# motor_board.net
KiCad netlist of a schematic drawn in EAGLE
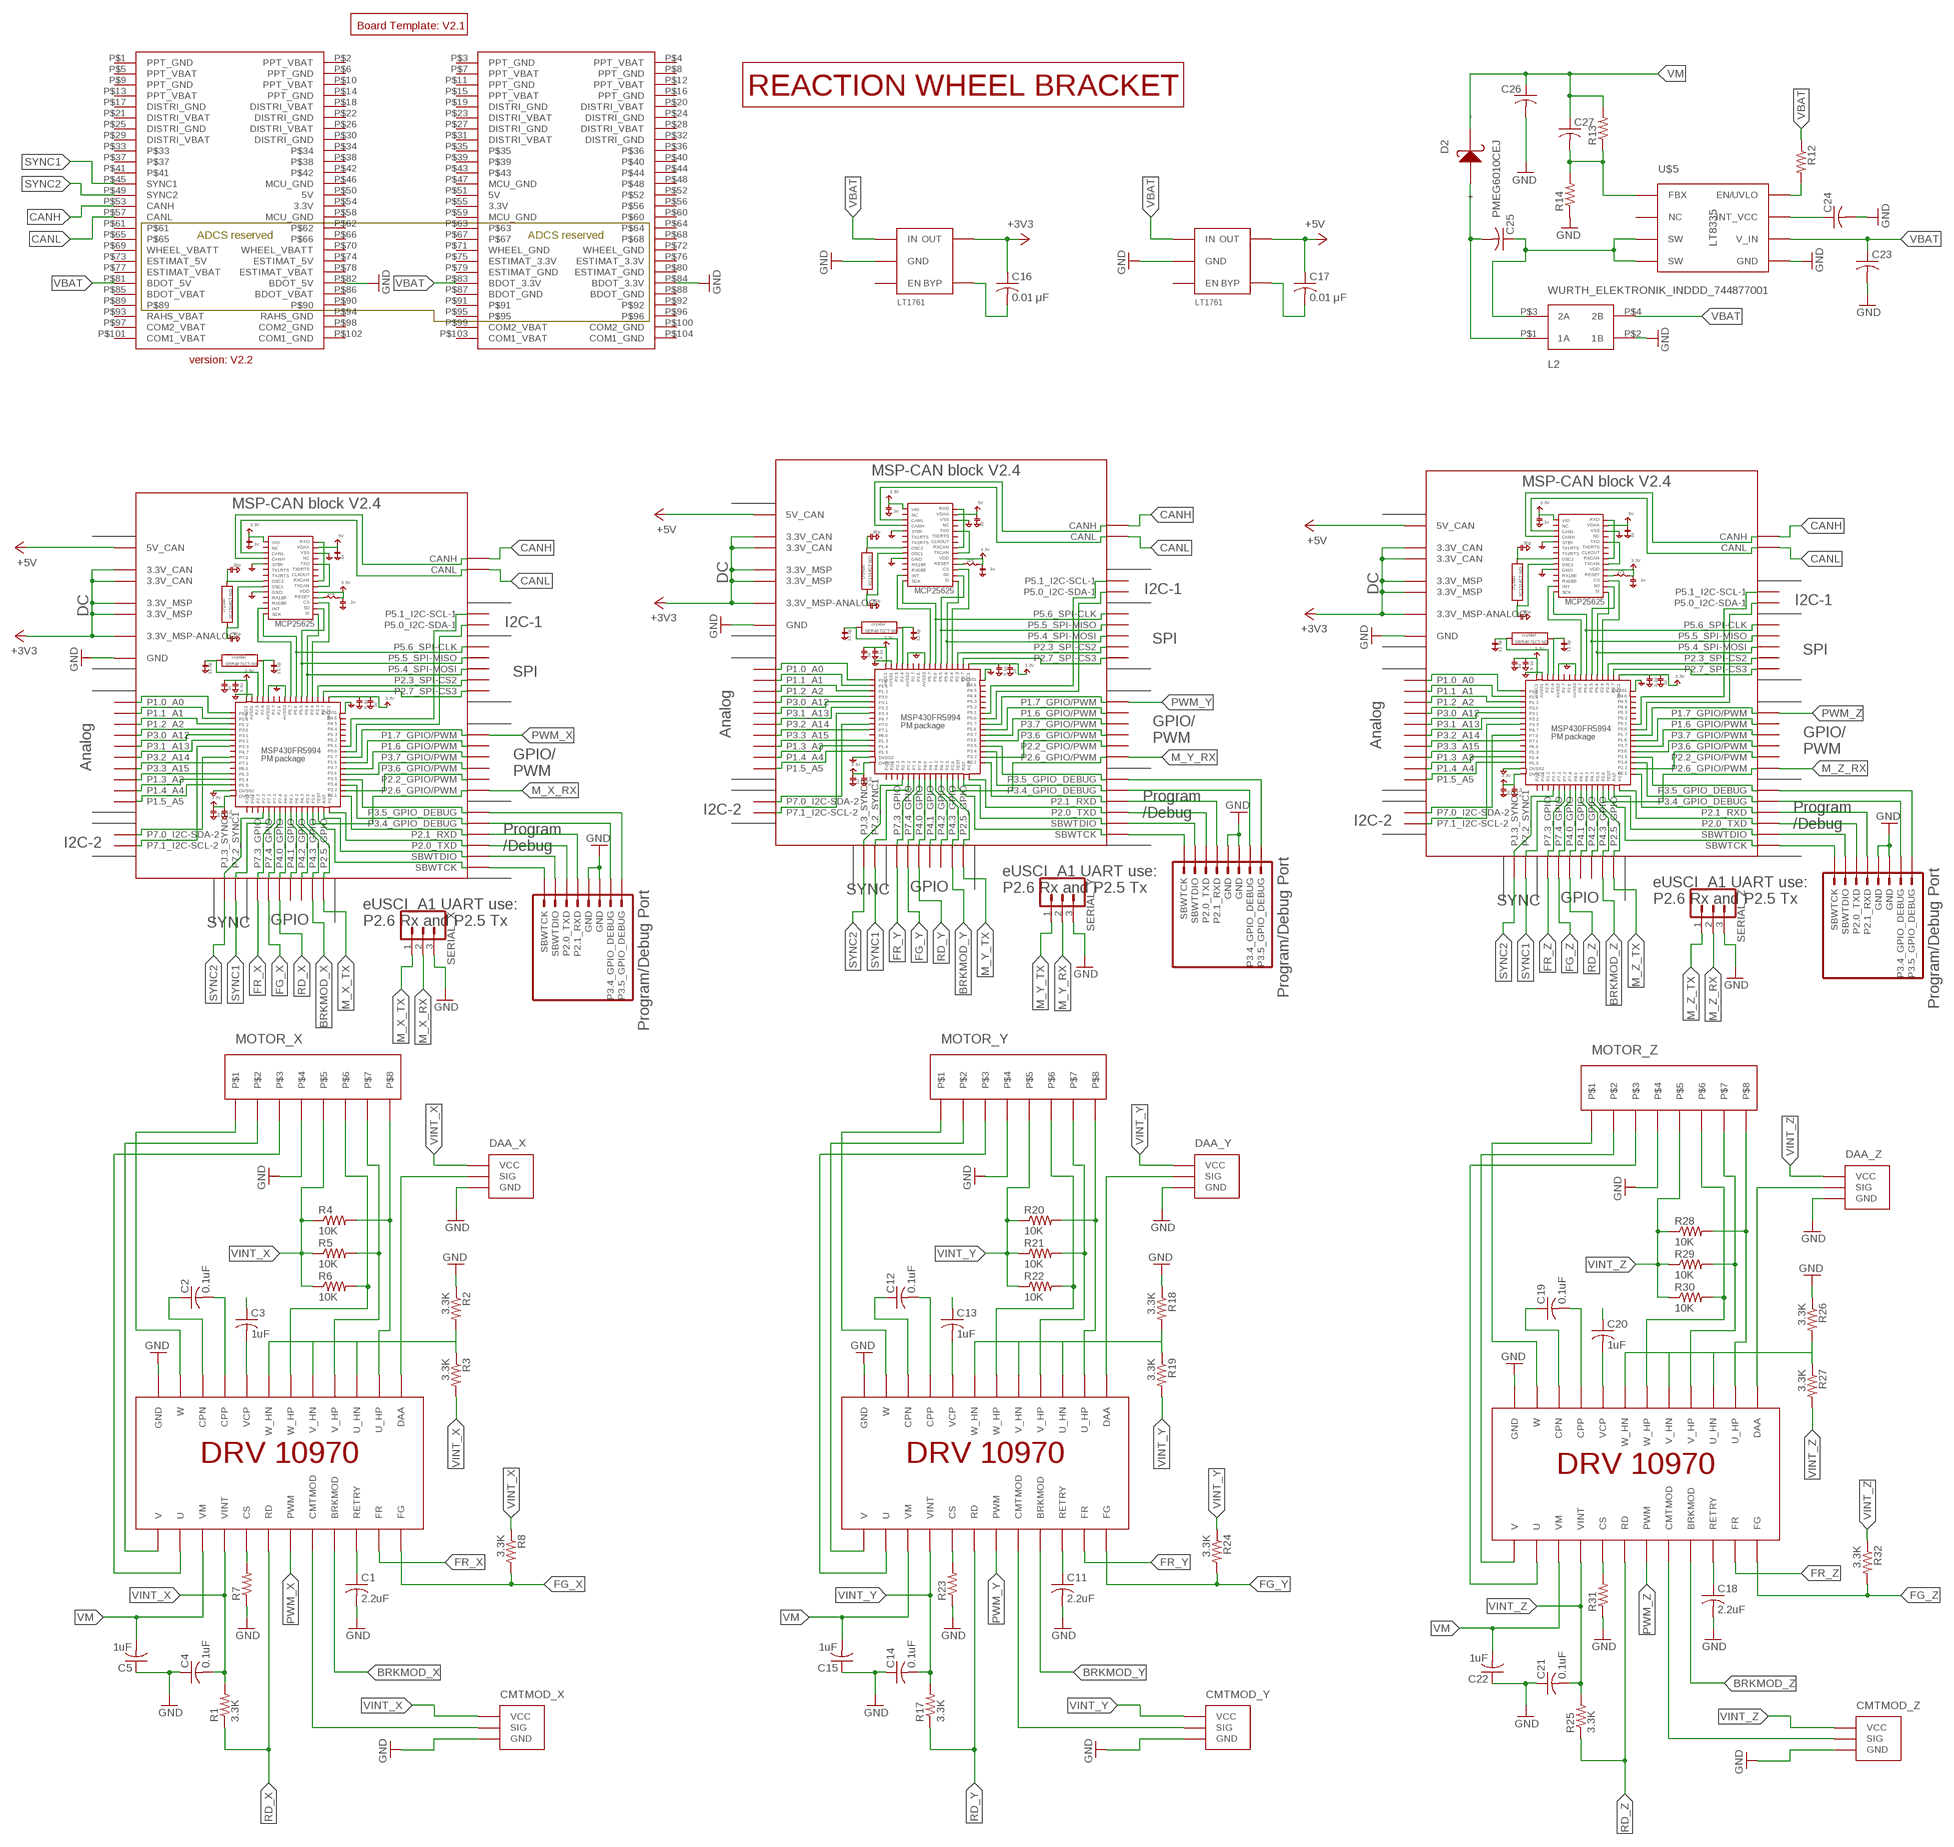
[diagram p0: schematic, sheet 1]

(export (version "E")
  (design (tool "Eeschema 10.0.6"))
  (components
    (comp (ref "C1")
      (value "2.2uF")
      (footprint "eagle-import:C1206")
      (libsource (lib "eagle-import") (part "C-USC1206"))
    )
    (comp (ref "C2")
      (value "0.1uF")
      (footprint "eagle-import:C0805")
      (libsource (lib "eagle-import") (part "C-USC0805"))
    )
    (comp (ref "C3")
      (value "1uF")
      (footprint "eagle-import:C1206")
      (libsource (lib "eagle-import") (part "C-USC1206"))
    )
    (comp (ref "C4")
      (value "0.1uF")
      (footprint "eagle-import:C0805")
      (libsource (lib "eagle-import") (part "C-USC0805"))
    )
    (comp (ref "C5")
      (value "1uF")
      (footprint "eagle-import:C1206")
      (libsource (lib "eagle-import") (part "C-USC1206"))
    )
    (comp (ref "C11")
      (value "2.2uF")
      (footprint "eagle-import:C1206")
      (libsource (lib "eagle-import") (part "C-USC1206"))
    )
    (comp (ref "C12")
      (value "0.1uF")
      (footprint "eagle-import:C0805")
      (libsource (lib "eagle-import") (part "C-USC0805"))
    )
    (comp (ref "C13")
      (value "1uF")
      (footprint "eagle-import:C1206")
      (libsource (lib "eagle-import") (part "C-USC1206"))
    )
    (comp (ref "C14")
      (value "0.1uF")
      (footprint "eagle-import:C0805")
      (libsource (lib "eagle-import") (part "C-USC0805"))
    )
    (comp (ref "C15")
      (value "1uF")
      (footprint "eagle-import:C1206")
      (libsource (lib "eagle-import") (part "C-USC1206"))
    )
    (comp (ref "C16")
      (value "0.01 μF")
      (footprint "eagle-import:C0805")
      (libsource (lib "eagle-import") (part "C-USC0805"))
    )
    (comp (ref "C17")
      (value "0.01 μF")
      (footprint "eagle-import:C0805")
      (libsource (lib "eagle-import") (part "C-USC0805"))
    )
    (comp (ref "C18")
      (value "2.2uF")
      (footprint "eagle-import:C1206")
      (libsource (lib "eagle-import") (part "C-USC1206"))
    )
    (comp (ref "C19")
      (value "0.1uF")
      (footprint "eagle-import:C0805")
      (libsource (lib "eagle-import") (part "C-USC0805"))
    )
    (comp (ref "C20")
      (value "1uF")
      (footprint "eagle-import:C1206")
      (libsource (lib "eagle-import") (part "C-USC1206"))
    )
    (comp (ref "C21")
      (value "0.1uF")
      (footprint "eagle-import:C0805")
      (libsource (lib "eagle-import") (part "C-USC0805"))
    )
    (comp (ref "C22")
      (value "1uF")
      (footprint "eagle-import:C1206")
      (libsource (lib "eagle-import") (part "C-USC1206"))
    )
    (comp (ref "C23")
      (value "C-USC0805")
      (footprint "eagle-import:C0805")
      (libsource (lib "eagle-import") (part "C-USC0805"))
    )
    (comp (ref "C24")
      (value "C-USC0805")
      (footprint "eagle-import:C0805")
      (libsource (lib "eagle-import") (part "C-USC0805"))
    )
    (comp (ref "C25")
      (value "C-USC0805")
      (footprint "eagle-import:C0805")
      (libsource (lib "eagle-import") (part "C-USC0805"))
    )
    (comp (ref "C26")
      (value "C-USC0805")
      (footprint "eagle-import:C0805")
      (libsource (lib "eagle-import") (part "C-USC0805"))
    )
    (comp (ref "C27")
      (value "C-USC0805")
      (footprint "eagle-import:C0805")
      (libsource (lib "eagle-import") (part "C-USC0805"))
    )
    (comp (ref "CMTMOD_X")
      (value "0_OHM_JUMPER")
      (footprint "eagle-import:0_OHM_JUMPER")
      (libsource (lib "eagle-import") (part "0_OHM_JUMPER"))
    )
    (comp (ref "CMTMOD_Y")
      (value "0_OHM_JUMPER")
      (footprint "eagle-import:0_OHM_JUMPER")
      (libsource (lib "eagle-import") (part "0_OHM_JUMPER"))
    )
    (comp (ref "CMTMOD_Z")
      (value "0_OHM_JUMPER")
      (footprint "eagle-import:0_OHM_JUMPER")
      (libsource (lib "eagle-import") (part "0_OHM_JUMPER"))
    )
    (comp (ref "D2")
      (value "PMEG6010CEJ")
      (footprint "eagle-import:SC-90")
      (libsource (lib "eagle-import") (part "PMEG6010CEJ"))
    )
    (comp (ref "DAA_X")
      (value "0_OHM_JUMPER")
      (footprint "eagle-import:0_OHM_JUMPER")
      (libsource (lib "eagle-import") (part "0_OHM_JUMPER"))
    )
    (comp (ref "DAA_Y")
      (value "0_OHM_JUMPER")
      (footprint "eagle-import:0_OHM_JUMPER")
      (libsource (lib "eagle-import") (part "0_OHM_JUMPER"))
    )
    (comp (ref "DAA_Z")
      (value "0_OHM_JUMPER")
      (footprint "eagle-import:0_OHM_JUMPER")
      (libsource (lib "eagle-import") (part "0_OHM_JUMPER"))
    )
    (comp (ref "L2")
      (value "WURTH_ELEKTRONIK_INDDD_744877001")
      (footprint "eagle-import:WURTH_ELEKTRONIK_INDDD_744877001")
      (libsource (lib "eagle-import") (part "WURTH_ELEKTRONIK_INDDD_744877001"))
    )
    (comp (ref "LDO_3V3")
      (value "LINEAR_LDO_LT1761-X")
      (footprint "eagle-import:SOT-23-5")
      (libsource (lib "eagle-import") (part "LINEAR_LDO_LT1761-X"))
    )
    (comp (ref "LDO_5V")
      (value "LINEAR_LDO_LT1761-X")
      (footprint "eagle-import:SOT-23-5")
      (libsource (lib "eagle-import") (part "LINEAR_LDO_LT1761-X"))
    )
    (comp (ref "MOTOR_X")
      (value "PICOLOCK_8")
      (footprint "eagle-import:PICOLOCK_8")
      (libsource (lib "eagle-import") (part "PICOLOCK_8"))
    )
    (comp (ref "MOTOR_Y")
      (value "PICOLOCK_8")
      (footprint "eagle-import:PICOLOCK_8")
      (libsource (lib "eagle-import") (part "PICOLOCK_8"))
    )
    (comp (ref "MOTOR_Z")
      (value "PICOLOCK_8")
      (footprint "eagle-import:PICOLOCK_8")
      (libsource (lib "eagle-import") (part "PICOLOCK_8"))
    )
    (comp (ref "R1")
      (value "3.3K")
      (footprint "eagle-import:R0805")
      (libsource (lib "eagle-import") (part "R-US_R0805"))
    )
    (comp (ref "R2")
      (value "3.3K")
      (footprint "eagle-import:R0805")
      (libsource (lib "eagle-import") (part "R-US_R0805"))
    )
    (comp (ref "R3")
      (value "3.3K")
      (footprint "eagle-import:R0805")
      (libsource (lib "eagle-import") (part "R-US_R0805"))
    )
    (comp (ref "R4")
      (value "10K")
      (footprint "eagle-import:R0805")
      (libsource (lib "eagle-import") (part "R-US_R0805"))
    )
    (comp (ref "R5")
      (value "10K")
      (footprint "eagle-import:R0805")
      (libsource (lib "eagle-import") (part "R-US_R0805"))
    )
    (comp (ref "R6")
      (value "10K")
      (footprint "eagle-import:R0805")
      (libsource (lib "eagle-import") (part "R-US_R0805"))
    )
    (comp (ref "R7")
      (value "R-US_R0805")
      (footprint "eagle-import:R0805")
      (libsource (lib "eagle-import") (part "R-US_R0805"))
    )
    (comp (ref "R8")
      (value "3.3K")
      (footprint "eagle-import:R0805")
      (libsource (lib "eagle-import") (part "R-US_R0805"))
    )
    (comp (ref "R12")
      (value "R-US_R0805")
      (footprint "eagle-import:R0805")
      (libsource (lib "eagle-import") (part "R-US_R0805"))
    )
    (comp (ref "R13")
      (value "R-US_R0805")
      (footprint "eagle-import:R0805")
      (libsource (lib "eagle-import") (part "R-US_R0805"))
    )
    (comp (ref "R14")
      (value "R-US_R0805")
      (footprint "eagle-import:R0805")
      (libsource (lib "eagle-import") (part "R-US_R0805"))
    )
    (comp (ref "R17")
      (value "3.3K")
      (footprint "eagle-import:R0805")
      (libsource (lib "eagle-import") (part "R-US_R0805"))
    )
    (comp (ref "R18")
      (value "3.3K")
      (footprint "eagle-import:R0805")
      (libsource (lib "eagle-import") (part "R-US_R0805"))
    )
    (comp (ref "R19")
      (value "3.3K")
      (footprint "eagle-import:R0805")
      (libsource (lib "eagle-import") (part "R-US_R0805"))
    )
    (comp (ref "R20")
      (value "10K")
      (footprint "eagle-import:R0805")
      (libsource (lib "eagle-import") (part "R-US_R0805"))
    )
    (comp (ref "R21")
      (value "10K")
      (footprint "eagle-import:R0805")
      (libsource (lib "eagle-import") (part "R-US_R0805"))
    )
    (comp (ref "R22")
      (value "10K")
      (footprint "eagle-import:R0805")
      (libsource (lib "eagle-import") (part "R-US_R0805"))
    )
    (comp (ref "R23")
      (value "R-US_R0805")
      (footprint "eagle-import:R0805")
      (libsource (lib "eagle-import") (part "R-US_R0805"))
    )
    (comp (ref "R24")
      (value "3.3K")
      (footprint "eagle-import:R0805")
      (libsource (lib "eagle-import") (part "R-US_R0805"))
    )
    (comp (ref "R25")
      (value "3.3K")
      (footprint "eagle-import:R0805")
      (libsource (lib "eagle-import") (part "R-US_R0805"))
    )
    (comp (ref "R26")
      (value "3.3K")
      (footprint "eagle-import:R0805")
      (libsource (lib "eagle-import") (part "R-US_R0805"))
    )
    (comp (ref "R27")
      (value "3.3K")
      (footprint "eagle-import:R0805")
      (libsource (lib "eagle-import") (part "R-US_R0805"))
    )
    (comp (ref "R28")
      (value "10K")
      (footprint "eagle-import:R0805")
      (libsource (lib "eagle-import") (part "R-US_R0805"))
    )
    (comp (ref "R29")
      (value "10K")
      (footprint "eagle-import:R0805")
      (libsource (lib "eagle-import") (part "R-US_R0805"))
    )
    (comp (ref "R30")
      (value "10K")
      (footprint "eagle-import:R0805")
      (libsource (lib "eagle-import") (part "R-US_R0805"))
    )
    (comp (ref "R31")
      (value "R-US_R0805")
      (footprint "eagle-import:R0805")
      (libsource (lib "eagle-import") (part "R-US_R0805"))
    )
    (comp (ref "R32")
      (value "3.3K")
      (footprint "eagle-import:R0805")
      (libsource (lib "eagle-import") (part "R-US_R0805"))
    )
    (comp (ref "SERIAL_X")
      (value "CONN_03LOCK")
      (footprint "eagle-import:1X03_LOCK")
      (libsource (lib "eagle-import") (part "CONN_03LOCK"))
    )
    (comp (ref "SERIAL_Y")
      (value "CONN_03LOCK")
      (footprint "eagle-import:1X03_LOCK")
      (libsource (lib "eagle-import") (part "CONN_03LOCK"))
    )
    (comp (ref "SERIAL_Z")
      (value "CONN_03LOCK")
      (footprint "eagle-import:1X03_LOCK")
      (libsource (lib "eagle-import") (part "CONN_03LOCK"))
    )
    (comp (ref "U$1")
      (value "BOARD_TEMPLATE")
      (footprint "eagle-import:BOARD_TEMPLATE")
      (libsource (lib "eagle-import") (part "BOARD_TEMPLATE"))
    )
    (comp (ref "U$2")
      (value "PC104_CONNECTOR")
      (footprint "eagle-import:PC104_CONNECTOR")
      (libsource (lib "eagle-import") (part "PC104_CONNECTOR"))
    )
    (comp (ref "U$3")
      (value "MSP-CAN_BLOCK")
      (footprint "eagle-import:MSP-CAN_BLOCK")
      (libsource (lib "eagle-import") (part "MSP-CAN_BLOCK"))
    )
    (comp (ref "U$4")
      (value "PROGRAM/DEBUG_PORT")
      (footprint "eagle-import:1X08_CONNECTOR")
      (libsource (lib "eagle-import") (part "PROGRAM/DEBUG_PORT"))
    )
    (comp (ref "U$5")
      (value "LT8335")
      (footprint "eagle-import:DDB")
      (libsource (lib "eagle-import") (part "LT8335"))
    )
    (comp (ref "U$7")
      (value "DRV10970")
      (footprint "eagle-import:DRV10970")
      (libsource (lib "eagle-import") (part "DRV10970"))
    )
    (comp (ref "U$9")
      (value "REACTION_WHEEL_BRACKET")
      (footprint "eagle-import:REACTION_WHEEL_BRACKET")
      (libsource (lib "eagle-import") (part "REACTION_WHEEL_BRACKET"))
    )
    (comp (ref "U$10")
      (value "MSP-CAN_BLOCK")
      (footprint "eagle-import:MSP-CAN_BLOCK")
      (libsource (lib "eagle-import") (part "MSP-CAN_BLOCK"))
    )
    (comp (ref "U$11")
      (value "PROGRAM/DEBUG_PORT")
      (footprint "eagle-import:1X08_CONNECTOR")
      (libsource (lib "eagle-import") (part "PROGRAM/DEBUG_PORT"))
    )
    (comp (ref "U$12")
      (value "DRV10970")
      (footprint "eagle-import:DRV10970")
      (libsource (lib "eagle-import") (part "DRV10970"))
    )
    (comp (ref "U$13")
      (value "MSP-CAN_BLOCK")
      (footprint "eagle-import:MSP-CAN_BLOCK")
      (libsource (lib "eagle-import") (part "MSP-CAN_BLOCK"))
    )
    (comp (ref "U$14")
      (value "PROGRAM/DEBUG_PORT")
      (footprint "eagle-import:1X08_CONNECTOR")
      (libsource (lib "eagle-import") (part "PROGRAM/DEBUG_PORT"))
    )
    (comp (ref "U$15")
      (value "DRV10970")
      (footprint "eagle-import:DRV10970")
      (libsource (lib "eagle-import") (part "DRV10970"))
    )
  )
  (nets
    (net (code "1") (name "+3V3") (class "Default")
      (node (ref "C16") (pin "1") (pinfunction "1_1") (pintype "passive"))
      (node (ref "LDO_3V3") (pin "P$5") (pinfunction "OUT_P$5") (pintype "bidirectional"))
      (node (ref "U$10") (pin "3.3V@CAN1") (pinfunction "3.3V_CAN_3.3V@CAN1") (pintype "bidirectional"))
      (node (ref "U$10") (pin "3.3V@CAN2") (pinfunction "3.3V_CAN_3.3V@CAN2") (pintype "bidirectional"))
      (node (ref "U$10") (pin "3.3V@MSP1") (pinfunction "3.3V_MSP_3.3V@MSP1") (pintype "bidirectional"))
      (node (ref "U$10") (pin "3.3V@MSP2") (pinfunction "3.3V_MSP_3.3V@MSP2") (pintype "bidirectional"))
      (node (ref "U$10") (pin "3.3V_ANALOG@MSP2") (pinfunction "3.3V_MSP-ANALOG_3.3V_ANALOG@MSP2") (pintype "bidirectional"))
      (node (ref "U$13") (pin "3.3V@CAN1") (pinfunction "3.3V_CAN_3.3V@CAN1") (pintype "bidirectional"))
      (node (ref "U$13") (pin "3.3V@CAN2") (pinfunction "3.3V_CAN_3.3V@CAN2") (pintype "bidirectional"))
      (node (ref "U$13") (pin "3.3V@MSP1") (pinfunction "3.3V_MSP_3.3V@MSP1") (pintype "bidirectional"))
      (node (ref "U$13") (pin "3.3V@MSP2") (pinfunction "3.3V_MSP_3.3V@MSP2") (pintype "bidirectional"))
      (node (ref "U$13") (pin "3.3V_ANALOG@MSP2") (pinfunction "3.3V_MSP-ANALOG_3.3V_ANALOG@MSP2") (pintype "bidirectional"))
      (node (ref "U$3") (pin "3.3V@CAN1") (pinfunction "3.3V_CAN_3.3V@CAN1") (pintype "bidirectional"))
      (node (ref "U$3") (pin "3.3V@CAN2") (pinfunction "3.3V_CAN_3.3V@CAN2") (pintype "bidirectional"))
      (node (ref "U$3") (pin "3.3V@MSP1") (pinfunction "3.3V_MSP_3.3V@MSP1") (pintype "bidirectional"))
      (node (ref "U$3") (pin "3.3V@MSP2") (pinfunction "3.3V_MSP_3.3V@MSP2") (pintype "bidirectional"))
      (node (ref "U$3") (pin "3.3V_ANALOG@MSP2") (pinfunction "3.3V_MSP-ANALOG_3.3V_ANALOG@MSP2") (pintype "bidirectional"))
    )
    (net (code "2") (name "+5V") (class "Default")
      (node (ref "C17") (pin "1") (pinfunction "1_1") (pintype "passive"))
      (node (ref "LDO_5V") (pin "P$5") (pinfunction "OUT_P$5") (pintype "bidirectional"))
      (node (ref "U$10") (pin "5V") (pinfunction "5V_CAN_5V") (pintype "bidirectional"))
      (node (ref "U$13") (pin "5V") (pinfunction "5V_CAN_5V") (pintype "bidirectional"))
      (node (ref "U$3") (pin "5V") (pinfunction "5V_CAN_5V") (pintype "bidirectional"))
    )
    (net (code "3") (name "BRKMOD_X") (class "Default")
      (node (ref "U$3") (pin "P4.3_GPIO") (pinfunction "P4.3_GPIO_P4.3_GPIO") (pintype "bidirectional"))
      (node (ref "U$7") (pin "BRKMOD") (pinfunction "BRKMOD_BRKMOD") (pintype "bidirectional"))
    )
    (net (code "4") (name "BRKMOD_Y") (class "Default")
      (node (ref "U$10") (pin "P4.3_GPIO") (pinfunction "P4.3_GPIO_P4.3_GPIO") (pintype "bidirectional"))
      (node (ref "U$12") (pin "BRKMOD") (pinfunction "BRKMOD_BRKMOD") (pintype "bidirectional"))
    )
    (net (code "5") (name "BRKMOD_Z") (class "Default")
      (node (ref "U$13") (pin "P4.3_GPIO") (pinfunction "P4.3_GPIO_P4.3_GPIO") (pintype "bidirectional"))
      (node (ref "U$15") (pin "BRKMOD") (pinfunction "BRKMOD_BRKMOD") (pintype "bidirectional"))
    )
    (net (code "6") (name "CANH") (class "Default")
      (node (ref "U$10") (pin "CANH") (pinfunction "CANH_CANH") (pintype "bidirectional"))
      (node (ref "U$13") (pin "CANH") (pinfunction "CANH_CANH") (pintype "bidirectional"))
      (node (ref "U$2") (pin "P$53") (pinfunction "CANH_P$53") (pintype "bidirectional"))
      (node (ref "U$3") (pin "CANH") (pinfunction "CANH_CANH") (pintype "bidirectional"))
    )
    (net (code "7") (name "CANL") (class "Default")
      (node (ref "U$10") (pin "CANL") (pinfunction "CANL_CANL") (pintype "bidirectional"))
      (node (ref "U$13") (pin "CANL") (pinfunction "CANL_CANL") (pintype "bidirectional"))
      (node (ref "U$2") (pin "P$57") (pinfunction "CANL_P$57") (pintype "bidirectional"))
      (node (ref "U$3") (pin "CANL") (pinfunction "CANL_CANL") (pintype "bidirectional"))
    )
    (net (code "8") (name "FG_X") (class "Default")
      (node (ref "R8") (pin "2") (pinfunction "2_2") (pintype "passive"))
      (node (ref "U$3") (pin "P7.4_GPIO") (pinfunction "P7.4_GPIO_P7.4_GPIO") (pintype "bidirectional"))
      (node (ref "U$7") (pin "FG") (pinfunction "FG_FG") (pintype "bidirectional"))
    )
    (net (code "9") (name "FG_Y") (class "Default")
      (node (ref "R24") (pin "2") (pinfunction "2_2") (pintype "passive"))
      (node (ref "U$10") (pin "P7.4_GPIO") (pinfunction "P7.4_GPIO_P7.4_GPIO") (pintype "bidirectional"))
      (node (ref "U$12") (pin "FG") (pinfunction "FG_FG") (pintype "bidirectional"))
    )
    (net (code "10") (name "FG_Z") (class "Default")
      (node (ref "R32") (pin "2") (pinfunction "2_2") (pintype "passive"))
      (node (ref "U$13") (pin "P7.4_GPIO") (pinfunction "P7.4_GPIO_P7.4_GPIO") (pintype "bidirectional"))
      (node (ref "U$15") (pin "FG") (pinfunction "FG_FG") (pintype "bidirectional"))
    )
    (net (code "11") (name "FR_X") (class "Default")
      (node (ref "U$3") (pin "P7.3_GPIO") (pinfunction "P7.3_GPIO_P7.3_GPIO") (pintype "bidirectional"))
      (node (ref "U$7") (pin "FR") (pinfunction "FR_FR") (pintype "bidirectional"))
    )
    (net (code "12") (name "FR_Y") (class "Default")
      (node (ref "U$10") (pin "P7.3_GPIO") (pinfunction "P7.3_GPIO_P7.3_GPIO") (pintype "bidirectional"))
      (node (ref "U$12") (pin "FR") (pinfunction "FR_FR") (pintype "bidirectional"))
    )
    (net (code "13") (name "FR_Z") (class "Default")
      (node (ref "U$13") (pin "P7.3_GPIO") (pinfunction "P7.3_GPIO_P7.3_GPIO") (pintype "bidirectional"))
      (node (ref "U$15") (pin "FR") (pinfunction "FR_FR") (pintype "bidirectional"))
    )
    (net (code "14") (name "GND") (class "Default")
      (node (ref "C1") (pin "2") (pinfunction "2_2") (pintype "passive"))
      (node (ref "C11") (pin "2") (pinfunction "2_2") (pintype "passive"))
      (node (ref "C13") (pin "1") (pinfunction "1_1") (pintype "passive"))
      (node (ref "C14") (pin "1") (pinfunction "1_1") (pintype "passive"))
      (node (ref "C15") (pin "1") (pinfunction "1_1") (pintype "passive"))
      (node (ref "C18") (pin "2") (pinfunction "2_2") (pintype "passive"))
      (node (ref "C20") (pin "1") (pinfunction "1_1") (pintype "passive"))
      (node (ref "C21") (pin "1") (pinfunction "1_1") (pintype "passive"))
      (node (ref "C22") (pin "1") (pinfunction "1_1") (pintype "passive"))
      (node (ref "C23") (pin "2") (pinfunction "2_2") (pintype "passive"))
      (node (ref "C24") (pin "2") (pinfunction "2_2") (pintype "passive"))
      (node (ref "C26") (pin "2") (pinfunction "2_2") (pintype "passive"))
      (node (ref "C3") (pin "1") (pinfunction "1_1") (pintype "passive"))
      (node (ref "C4") (pin "1") (pinfunction "1_1") (pintype "passive"))
      (node (ref "C5") (pin "1") (pinfunction "1_1") (pintype "passive"))
      (node (ref "CMTMOD_X") (pin "P$1") (pinfunction "GND_P$1") (pintype "bidirectional"))
      (node (ref "CMTMOD_Y") (pin "P$1") (pinfunction "GND_P$1") (pintype "bidirectional"))
      (node (ref "CMTMOD_Z") (pin "P$1") (pinfunction "GND_P$1") (pintype "bidirectional"))
      (node (ref "DAA_X") (pin "P$1") (pinfunction "GND_P$1") (pintype "bidirectional"))
      (node (ref "DAA_Y") (pin "P$1") (pinfunction "GND_P$1") (pintype "bidirectional"))
      (node (ref "DAA_Z") (pin "P$1") (pinfunction "GND_P$1") (pintype "bidirectional"))
      (node (ref "L2") (pin "P$2") (pinfunction "1B_P$2") (pintype "bidirectional"))
      (node (ref "LDO_3V3") (pin "P$2") (pinfunction "GND_P$2") (pintype "bidirectional"))
      (node (ref "LDO_5V") (pin "P$2") (pinfunction "GND_P$2") (pintype "bidirectional"))
      (node (ref "MOTOR_X") (pin "P$4") (pinfunction "P$4_P$4") (pintype "bidirectional"))
      (node (ref "MOTOR_Y") (pin "P$4") (pinfunction "P$4_P$4") (pintype "bidirectional"))
      (node (ref "MOTOR_Z") (pin "P$4") (pinfunction "P$4_P$4") (pintype "bidirectional"))
      (node (ref "R14") (pin "1") (pinfunction "1_1") (pintype "passive"))
      (node (ref "R18") (pin "1") (pinfunction "1_1") (pintype "passive"))
      (node (ref "R2") (pin "1") (pinfunction "1_1") (pintype "passive"))
      (node (ref "R23") (pin "1") (pinfunction "1_1") (pintype "passive"))
      (node (ref "R26") (pin "1") (pinfunction "1_1") (pintype "passive"))
      (node (ref "R31") (pin "1") (pinfunction "1_1") (pintype "passive"))
      (node (ref "R7") (pin "1") (pinfunction "1_1") (pintype "passive"))
      (node (ref "SERIAL_X") (pin "3") (pinfunction "3_3") (pintype "passive"))
      (node (ref "SERIAL_Y") (pin "3") (pinfunction "3_3") (pintype "passive"))
      (node (ref "SERIAL_Z") (pin "3") (pinfunction "3_3") (pintype "passive"))
      (node (ref "U$10") (pin "GND@1") (pinfunction "GND_GND@1") (pintype "bidirectional"))
      (node (ref "U$10") (pin "GND@10") (pinfunction "GND_GND@10") (pintype "bidirectional"))
      (node (ref "U$10") (pin "GND@11") (pinfunction "GND_GND@11") (pintype "bidirectional"))
      (node (ref "U$10") (pin "GND@12") (pinfunction "GND_GND@12") (pintype "bidirectional"))
      (node (ref "U$10") (pin "GND@13") (pinfunction "GND_GND@13") (pintype "bidirectional"))
      (node (ref "U$10") (pin "GND@14") (pinfunction "GND_GND@14") (pintype "bidirectional"))
      (node (ref "U$10") (pin "GND@15") (pinfunction "GND_GND@15") (pintype "bidirectional"))
      (node (ref "U$10") (pin "GND@16") (pinfunction "GND_GND@16") (pintype "bidirectional"))
      (node (ref "U$10") (pin "GND@17") (pinfunction "GND_GND@17") (pintype "bidirectional"))
      (node (ref "U$10") (pin "GND@2") (pinfunction "GND_GND@2") (pintype "bidirectional"))
      (node (ref "U$10") (pin "GND@26") (pinfunction "GND_GND@26") (pintype "bidirectional"))
      (node (ref "U$10") (pin "GND@3") (pinfunction "GND_GND@3") (pintype "bidirectional"))
      (node (ref "U$10") (pin "GND@4") (pinfunction "GND_GND@4") (pintype "bidirectional"))
      (node (ref "U$10") (pin "GND@5") (pinfunction "GND_GND@5") (pintype "bidirectional"))
      (node (ref "U$10") (pin "GND@7") (pinfunction "GND_GND@7") (pintype "bidirectional"))
      (node (ref "U$10") (pin "GND@8") (pinfunction "GND_GND@8") (pintype "bidirectional"))
      (node (ref "U$10") (pin "GND@9") (pinfunction "GND_GND@9") (pintype "bidirectional"))
      (node (ref "U$11") (pin "5") (pinfunction "GND_5") (pintype "bidirectional"))
      (node (ref "U$11") (pin "6") (pinfunction "GND_6") (pintype "bidirectional"))
      (node (ref "U$12") (pin "GND@1") (pinfunction "GND_GND@1") (pintype "bidirectional"))
      (node (ref "U$12") (pin "GND@2") (pinfunction "GND_GND@2") (pintype "bidirectional"))
      (node (ref "U$13") (pin "GND@1") (pinfunction "GND_GND@1") (pintype "bidirectional"))
      (node (ref "U$13") (pin "GND@10") (pinfunction "GND_GND@10") (pintype "bidirectional"))
      (node (ref "U$13") (pin "GND@11") (pinfunction "GND_GND@11") (pintype "bidirectional"))
      (node (ref "U$13") (pin "GND@12") (pinfunction "GND_GND@12") (pintype "bidirectional"))
      (node (ref "U$13") (pin "GND@13") (pinfunction "GND_GND@13") (pintype "bidirectional"))
      (node (ref "U$13") (pin "GND@14") (pinfunction "GND_GND@14") (pintype "bidirectional"))
      (node (ref "U$13") (pin "GND@15") (pinfunction "GND_GND@15") (pintype "bidirectional"))
      (node (ref "U$13") (pin "GND@16") (pinfunction "GND_GND@16") (pintype "bidirectional"))
      (node (ref "U$13") (pin "GND@17") (pinfunction "GND_GND@17") (pintype "bidirectional"))
      (node (ref "U$13") (pin "GND@2") (pinfunction "GND_GND@2") (pintype "bidirectional"))
      (node (ref "U$13") (pin "GND@26") (pinfunction "GND_GND@26") (pintype "bidirectional"))
      (node (ref "U$13") (pin "GND@3") (pinfunction "GND_GND@3") (pintype "bidirectional"))
      (node (ref "U$13") (pin "GND@4") (pinfunction "GND_GND@4") (pintype "bidirectional"))
      (node (ref "U$13") (pin "GND@5") (pinfunction "GND_GND@5") (pintype "bidirectional"))
      (node (ref "U$13") (pin "GND@7") (pinfunction "GND_GND@7") (pintype "bidirectional"))
      (node (ref "U$13") (pin "GND@8") (pinfunction "GND_GND@8") (pintype "bidirectional"))
      (node (ref "U$13") (pin "GND@9") (pinfunction "GND_GND@9") (pintype "bidirectional"))
      (node (ref "U$14") (pin "5") (pinfunction "GND_5") (pintype "bidirectional"))
      (node (ref "U$14") (pin "6") (pinfunction "GND_6") (pintype "bidirectional"))
      (node (ref "U$15") (pin "GND@1") (pinfunction "GND_GND@1") (pintype "bidirectional"))
      (node (ref "U$15") (pin "GND@2") (pinfunction "GND_GND@2") (pintype "bidirectional"))
      (node (ref "U$2") (pin "P$82") (pinfunction "BDOT_5V_P$82") (pintype "bidirectional"))
      (node (ref "U$2") (pin "P$84") (pinfunction "BDOT_3.3V_P$84") (pintype "bidirectional"))
      (node (ref "U$3") (pin "GND@1") (pinfunction "GND_GND@1") (pintype "bidirectional"))
      (node (ref "U$3") (pin "GND@10") (pinfunction "GND_GND@10") (pintype "bidirectional"))
      (node (ref "U$3") (pin "GND@11") (pinfunction "GND_GND@11") (pintype "bidirectional"))
      (node (ref "U$3") (pin "GND@12") (pinfunction "GND_GND@12") (pintype "bidirectional"))
      (node (ref "U$3") (pin "GND@13") (pinfunction "GND_GND@13") (pintype "bidirectional"))
      (node (ref "U$3") (pin "GND@14") (pinfunction "GND_GND@14") (pintype "bidirectional"))
      (node (ref "U$3") (pin "GND@15") (pinfunction "GND_GND@15") (pintype "bidirectional"))
      (node (ref "U$3") (pin "GND@16") (pinfunction "GND_GND@16") (pintype "bidirectional"))
      (node (ref "U$3") (pin "GND@17") (pinfunction "GND_GND@17") (pintype "bidirectional"))
      (node (ref "U$3") (pin "GND@2") (pinfunction "GND_GND@2") (pintype "bidirectional"))
      (node (ref "U$3") (pin "GND@26") (pinfunction "GND_GND@26") (pintype "bidirectional"))
      (node (ref "U$3") (pin "GND@3") (pinfunction "GND_GND@3") (pintype "bidirectional"))
      (node (ref "U$3") (pin "GND@4") (pinfunction "GND_GND@4") (pintype "bidirectional"))
      (node (ref "U$3") (pin "GND@5") (pinfunction "GND_GND@5") (pintype "bidirectional"))
      (node (ref "U$3") (pin "GND@7") (pinfunction "GND_GND@7") (pintype "bidirectional"))
      (node (ref "U$3") (pin "GND@8") (pinfunction "GND_GND@8") (pintype "bidirectional"))
      (node (ref "U$3") (pin "GND@9") (pinfunction "GND_GND@9") (pintype "bidirectional"))
      (node (ref "U$4") (pin "5") (pinfunction "GND_5") (pintype "bidirectional"))
      (node (ref "U$4") (pin "6") (pinfunction "GND_6") (pintype "bidirectional"))
      (node (ref "U$5") (pin "GND") (pinfunction "GND_GND") (pintype "bidirectional"))
      (node (ref "U$5") (pin "P$5") (pinfunction "GND_P$5") (pintype "bidirectional"))
      (node (ref "U$7") (pin "GND@1") (pinfunction "GND_GND@1") (pintype "bidirectional"))
      (node (ref "U$7") (pin "GND@2") (pinfunction "GND_GND@2") (pintype "bidirectional"))
    )
    (net (code "15") (name "M_X_RX") (class "Default")
      (node (ref "SERIAL_X") (pin "2") (pinfunction "2_2") (pintype "passive"))
      (node (ref "U$3") (pin "P2.6_GPIO/PWM") (pinfunction "P2.6_GPIO/PWM_P2.6_GPIO/PWM") (pintype "bidirectional"))
    )
    (net (code "16") (name "M_X_TX") (class "Default")
      (node (ref "SERIAL_X") (pin "1") (pinfunction "1_1") (pintype "passive"))
      (node (ref "U$3") (pin "P2.5_GPIO") (pinfunction "P2.5_GPIO_P2.5_GPIO") (pintype "bidirectional"))
    )
    (net (code "17") (name "M_Y_RX") (class "Default")
      (node (ref "SERIAL_Y") (pin "2") (pinfunction "2_2") (pintype "passive"))
      (node (ref "U$10") (pin "P2.6_GPIO/PWM") (pinfunction "P2.6_GPIO/PWM_P2.6_GPIO/PWM") (pintype "bidirectional"))
    )
    (net (code "18") (name "M_Y_TX") (class "Default")
      (node (ref "SERIAL_Y") (pin "1") (pinfunction "1_1") (pintype "passive"))
      (node (ref "U$10") (pin "P2.5_GPIO") (pinfunction "P2.5_GPIO_P2.5_GPIO") (pintype "bidirectional"))
    )
    (net (code "19") (name "M_Z_RX") (class "Default")
      (node (ref "SERIAL_Z") (pin "2") (pinfunction "2_2") (pintype "passive"))
      (node (ref "U$13") (pin "P2.6_GPIO/PWM") (pinfunction "P2.6_GPIO/PWM_P2.6_GPIO/PWM") (pintype "bidirectional"))
    )
    (net (code "20") (name "M_Z_TX") (class "Default")
      (node (ref "SERIAL_Z") (pin "1") (pinfunction "1_1") (pintype "passive"))
      (node (ref "U$13") (pin "P2.5_GPIO") (pinfunction "P2.5_GPIO_P2.5_GPIO") (pintype "bidirectional"))
    )
    (net (code "21") (name "Net-(C1-Pad1)") (class "Default")
      (node (ref "C1") (pin "1") (pinfunction "1_1") (pintype "passive"))
      (node (ref "U$7") (pin "RETRY") (pinfunction "RETRY_RETRY") (pintype "bidirectional"))
    )
    (net (code "22") (name "Net-(C2-Pad1)") (class "Default")
      (node (ref "C2") (pin "1") (pinfunction "1_1") (pintype "passive"))
      (node (ref "U$7") (pin "CPN") (pinfunction "CPN_CPN") (pintype "bidirectional"))
    )
    (net (code "23") (name "Net-(C2-Pad2)") (class "Default")
      (node (ref "C2") (pin "2") (pinfunction "2_2") (pintype "passive"))
      (node (ref "U$7") (pin "CPP") (pinfunction "CPP_CPP") (pintype "bidirectional"))
    )
    (net (code "24") (name "Net-(C3-Pad2)") (class "Default")
      (node (ref "C3") (pin "2") (pinfunction "2_2") (pintype "passive"))
      (node (ref "U$7") (pin "VCP") (pinfunction "VCP_VCP") (pintype "bidirectional"))
    )
    (net (code "25") (name "Net-(C11-Pad1)") (class "Default")
      (node (ref "C11") (pin "1") (pinfunction "1_1") (pintype "passive"))
      (node (ref "U$12") (pin "RETRY") (pinfunction "RETRY_RETRY") (pintype "bidirectional"))
    )
    (net (code "26") (name "Net-(C12-Pad1)") (class "Default")
      (node (ref "C12") (pin "1") (pinfunction "1_1") (pintype "passive"))
      (node (ref "U$12") (pin "CPN") (pinfunction "CPN_CPN") (pintype "bidirectional"))
    )
    (net (code "27") (name "Net-(C12-Pad2)") (class "Default")
      (node (ref "C12") (pin "2") (pinfunction "2_2") (pintype "passive"))
      (node (ref "U$12") (pin "CPP") (pinfunction "CPP_CPP") (pintype "bidirectional"))
    )
    (net (code "28") (name "Net-(C13-Pad2)") (class "Default")
      (node (ref "C13") (pin "2") (pinfunction "2_2") (pintype "passive"))
      (node (ref "U$12") (pin "VCP") (pinfunction "VCP_VCP") (pintype "bidirectional"))
    )
    (net (code "29") (name "Net-(C18-Pad1)") (class "Default")
      (node (ref "C18") (pin "1") (pinfunction "1_1") (pintype "passive"))
      (node (ref "U$15") (pin "RETRY") (pinfunction "RETRY_RETRY") (pintype "bidirectional"))
    )
    (net (code "30") (name "Net-(C19-Pad1)") (class "Default")
      (node (ref "C19") (pin "1") (pinfunction "1_1") (pintype "passive"))
      (node (ref "U$15") (pin "CPN") (pinfunction "CPN_CPN") (pintype "bidirectional"))
    )
    (net (code "31") (name "Net-(C19-Pad2)") (class "Default")
      (node (ref "C19") (pin "2") (pinfunction "2_2") (pintype "passive"))
      (node (ref "U$15") (pin "CPP") (pinfunction "CPP_CPP") (pintype "bidirectional"))
    )
    (net (code "32") (name "Net-(C20-Pad2)") (class "Default")
      (node (ref "C20") (pin "2") (pinfunction "2_2") (pintype "passive"))
      (node (ref "U$15") (pin "VCP") (pinfunction "VCP_VCP") (pintype "bidirectional"))
    )
    (net (code "33") (name "Net-(CMTMOD_X-SIG)") (class "Default")
      (node (ref "CMTMOD_X") (pin "P$2") (pinfunction "SIG_P$2") (pintype "bidirectional"))
      (node (ref "U$7") (pin "CMTMOD") (pinfunction "CMTMOD_CMTMOD") (pintype "bidirectional"))
    )
    (net (code "34") (name "Net-(CMTMOD_Y-SIG)") (class "Default")
      (node (ref "CMTMOD_Y") (pin "P$2") (pinfunction "SIG_P$2") (pintype "bidirectional"))
      (node (ref "U$12") (pin "CMTMOD") (pinfunction "CMTMOD_CMTMOD") (pintype "bidirectional"))
    )
    (net (code "35") (name "Net-(CMTMOD_Z-SIG)") (class "Default")
      (node (ref "CMTMOD_Z") (pin "P$2") (pinfunction "SIG_P$2") (pintype "bidirectional"))
      (node (ref "U$15") (pin "CMTMOD") (pinfunction "CMTMOD_CMTMOD") (pintype "bidirectional"))
    )
    (net (code "36") (name "Net-(D2-+)") (class "Default")
      (node (ref "C25") (pin "2") (pinfunction "2_2") (pintype "passive"))
      (node (ref "D2") (pin "P$1") (pinfunction "+_P$1") (pintype "bidirectional"))
      (node (ref "L2") (pin "P$1") (pinfunction "1A_P$1") (pintype "bidirectional"))
    )
    (net (code "37") (name "Net-(DAA_X-SIG)") (class "Default")
      (node (ref "DAA_X") (pin "P$2") (pinfunction "SIG_P$2") (pintype "bidirectional"))
      (node (ref "U$7") (pin "DAA") (pinfunction "DAA_DAA") (pintype "bidirectional"))
    )
    (net (code "38") (name "Net-(DAA_Y-SIG)") (class "Default")
      (node (ref "DAA_Y") (pin "P$2") (pinfunction "SIG_P$2") (pintype "bidirectional"))
      (node (ref "U$12") (pin "DAA") (pinfunction "DAA_DAA") (pintype "bidirectional"))
    )
    (net (code "39") (name "Net-(DAA_Z-SIG)") (class "Default")
      (node (ref "DAA_Z") (pin "P$2") (pinfunction "SIG_P$2") (pintype "bidirectional"))
      (node (ref "U$15") (pin "DAA") (pinfunction "DAA_DAA") (pintype "bidirectional"))
    )
    (net (code "40") (name "Net-(L2-2A)") (class "Default")
      (node (ref "C25") (pin "1") (pinfunction "1_1") (pintype "passive"))
      (node (ref "L2") (pin "P$3") (pinfunction "2A_P$3") (pintype "bidirectional"))
      (node (ref "U$5") (pin "P$3") (pinfunction "SW_P$3") (pintype "bidirectional"))
      (node (ref "U$5") (pin "P$4") (pinfunction "SW_P$4") (pintype "bidirectional"))
    )
    (net (code "41") (name "Net-(LDO_3V3-BYP)") (class "Default")
      (node (ref "C16") (pin "2") (pinfunction "2_2") (pintype "passive"))
      (node (ref "LDO_3V3") (pin "P$4") (pinfunction "BYP_P$4") (pintype "bidirectional"))
    )
    (net (code "42") (name "Net-(LDO_5V-BYP)") (class "Default")
      (node (ref "C17") (pin "2") (pinfunction "2_2") (pintype "passive"))
      (node (ref "LDO_5V") (pin "P$4") (pinfunction "BYP_P$4") (pintype "bidirectional"))
    )
    (net (code "43") (name "Net-(MOTOR_X-PadP$1)") (class "Default")
      (node (ref "MOTOR_X") (pin "P$1") (pinfunction "P$1_P$1") (pintype "bidirectional"))
      (node (ref "U$7") (pin "W") (pinfunction "W_W") (pintype "bidirectional"))
    )
    (net (code "44") (name "Net-(MOTOR_X-PadP$2)") (class "Default")
      (node (ref "MOTOR_X") (pin "P$2") (pinfunction "P$2_P$2") (pintype "bidirectional"))
      (node (ref "U$7") (pin "V") (pinfunction "V_V") (pintype "bidirectional"))
    )
    (net (code "45") (name "Net-(MOTOR_X-PadP$3)") (class "Default")
      (node (ref "MOTOR_X") (pin "P$3") (pinfunction "P$3_P$3") (pintype "bidirectional"))
      (node (ref "U$7") (pin "U") (pinfunction "U_U") (pintype "bidirectional"))
    )
    (net (code "46") (name "Net-(MOTOR_X-PadP$6)") (class "Default")
      (node (ref "MOTOR_X") (pin "P$6") (pinfunction "P$6_P$6") (pintype "bidirectional"))
      (node (ref "R6") (pin "2") (pinfunction "2_2") (pintype "passive"))
      (node (ref "U$7") (pin "W_HP") (pinfunction "W_HP_W_HP") (pintype "bidirectional"))
    )
    (net (code "47") (name "Net-(MOTOR_X-PadP$7)") (class "Default")
      (node (ref "MOTOR_X") (pin "P$7") (pinfunction "P$7_P$7") (pintype "bidirectional"))
      (node (ref "R5") (pin "2") (pinfunction "2_2") (pintype "passive"))
      (node (ref "U$7") (pin "V_HP") (pinfunction "V_HP_V_HP") (pintype "bidirectional"))
    )
    (net (code "48") (name "Net-(MOTOR_X-PadP$8)") (class "Default")
      (node (ref "MOTOR_X") (pin "P$8") (pinfunction "P$8_P$8") (pintype "bidirectional"))
      (node (ref "R4") (pin "2") (pinfunction "2_2") (pintype "passive"))
      (node (ref "U$7") (pin "U_HP") (pinfunction "U_HP_U_HP") (pintype "bidirectional"))
    )
    (net (code "49") (name "Net-(MOTOR_Y-PadP$1)") (class "Default")
      (node (ref "MOTOR_Y") (pin "P$1") (pinfunction "P$1_P$1") (pintype "bidirectional"))
      (node (ref "U$12") (pin "W") (pinfunction "W_W") (pintype "bidirectional"))
    )
    (net (code "50") (name "Net-(MOTOR_Y-PadP$2)") (class "Default")
      (node (ref "MOTOR_Y") (pin "P$2") (pinfunction "P$2_P$2") (pintype "bidirectional"))
      (node (ref "U$12") (pin "V") (pinfunction "V_V") (pintype "bidirectional"))
    )
    (net (code "51") (name "Net-(MOTOR_Y-PadP$3)") (class "Default")
      (node (ref "MOTOR_Y") (pin "P$3") (pinfunction "P$3_P$3") (pintype "bidirectional"))
      (node (ref "U$12") (pin "U") (pinfunction "U_U") (pintype "bidirectional"))
    )
    (net (code "52") (name "Net-(MOTOR_Y-PadP$6)") (class "Default")
      (node (ref "MOTOR_Y") (pin "P$6") (pinfunction "P$6_P$6") (pintype "bidirectional"))
      (node (ref "R22") (pin "2") (pinfunction "2_2") (pintype "passive"))
      (node (ref "U$12") (pin "W_HP") (pinfunction "W_HP_W_HP") (pintype "bidirectional"))
    )
    (net (code "53") (name "Net-(MOTOR_Y-PadP$7)") (class "Default")
      (node (ref "MOTOR_Y") (pin "P$7") (pinfunction "P$7_P$7") (pintype "bidirectional"))
      (node (ref "R21") (pin "2") (pinfunction "2_2") (pintype "passive"))
      (node (ref "U$12") (pin "V_HP") (pinfunction "V_HP_V_HP") (pintype "bidirectional"))
    )
    (net (code "54") (name "Net-(MOTOR_Y-PadP$8)") (class "Default")
      (node (ref "MOTOR_Y") (pin "P$8") (pinfunction "P$8_P$8") (pintype "bidirectional"))
      (node (ref "R20") (pin "2") (pinfunction "2_2") (pintype "passive"))
      (node (ref "U$12") (pin "U_HP") (pinfunction "U_HP_U_HP") (pintype "bidirectional"))
    )
    (net (code "55") (name "Net-(MOTOR_Z-PadP$1)") (class "Default")
      (node (ref "MOTOR_Z") (pin "P$1") (pinfunction "P$1_P$1") (pintype "bidirectional"))
      (node (ref "U$15") (pin "W") (pinfunction "W_W") (pintype "bidirectional"))
    )
    (net (code "56") (name "Net-(MOTOR_Z-PadP$2)") (class "Default")
      (node (ref "MOTOR_Z") (pin "P$2") (pinfunction "P$2_P$2") (pintype "bidirectional"))
      (node (ref "U$15") (pin "V") (pinfunction "V_V") (pintype "bidirectional"))
    )
    (net (code "57") (name "Net-(MOTOR_Z-PadP$3)") (class "Default")
      (node (ref "MOTOR_Z") (pin "P$3") (pinfunction "P$3_P$3") (pintype "bidirectional"))
      (node (ref "U$15") (pin "U") (pinfunction "U_U") (pintype "bidirectional"))
    )
    (net (code "58") (name "Net-(MOTOR_Z-PadP$6)") (class "Default")
      (node (ref "MOTOR_Z") (pin "P$6") (pinfunction "P$6_P$6") (pintype "bidirectional"))
      (node (ref "R30") (pin "2") (pinfunction "2_2") (pintype "passive"))
      (node (ref "U$15") (pin "W_HP") (pinfunction "W_HP_W_HP") (pintype "bidirectional"))
    )
    (net (code "59") (name "Net-(MOTOR_Z-PadP$7)") (class "Default")
      (node (ref "MOTOR_Z") (pin "P$7") (pinfunction "P$7_P$7") (pintype "bidirectional"))
      (node (ref "R29") (pin "2") (pinfunction "2_2") (pintype "passive"))
      (node (ref "U$15") (pin "V_HP") (pinfunction "V_HP_V_HP") (pintype "bidirectional"))
    )
    (net (code "60") (name "Net-(MOTOR_Z-PadP$8)") (class "Default")
      (node (ref "MOTOR_Z") (pin "P$8") (pinfunction "P$8_P$8") (pintype "bidirectional"))
      (node (ref "R28") (pin "2") (pinfunction "2_2") (pintype "passive"))
      (node (ref "U$15") (pin "U_HP") (pinfunction "U_HP_U_HP") (pintype "bidirectional"))
    )
    (net (code "61") (name "Net-(R2-Pad2)") (class "Default")
      (node (ref "R2") (pin "2") (pinfunction "2_2") (pintype "passive"))
      (node (ref "R3") (pin "1") (pinfunction "1_1") (pintype "passive"))
      (node (ref "U$7") (pin "U_HN") (pinfunction "U_HN_U_HN") (pintype "bidirectional"))
      (node (ref "U$7") (pin "V_HN") (pinfunction "V_HN_V_HN") (pintype "bidirectional"))
      (node (ref "U$7") (pin "W_HN") (pinfunction "W_HN_W_HN") (pintype "bidirectional"))
    )
    (net (code "62") (name "Net-(R7-Pad2)") (class "Default")
      (node (ref "R7") (pin "2") (pinfunction "2_2") (pintype "passive"))
      (node (ref "U$7") (pin "CS") (pinfunction "CS_CS") (pintype "bidirectional"))
    )
    (net (code "63") (name "Net-(R18-Pad2)") (class "Default")
      (node (ref "R18") (pin "2") (pinfunction "2_2") (pintype "passive"))
      (node (ref "R19") (pin "1") (pinfunction "1_1") (pintype "passive"))
      (node (ref "U$12") (pin "U_HN") (pinfunction "U_HN_U_HN") (pintype "bidirectional"))
      (node (ref "U$12") (pin "V_HN") (pinfunction "V_HN_V_HN") (pintype "bidirectional"))
      (node (ref "U$12") (pin "W_HN") (pinfunction "W_HN_W_HN") (pintype "bidirectional"))
    )
    (net (code "64") (name "Net-(R23-Pad2)") (class "Default")
      (node (ref "R23") (pin "2") (pinfunction "2_2") (pintype "passive"))
      (node (ref "U$12") (pin "CS") (pinfunction "CS_CS") (pintype "bidirectional"))
    )
    (net (code "65") (name "Net-(R26-Pad2)") (class "Default")
      (node (ref "R26") (pin "2") (pinfunction "2_2") (pintype "passive"))
      (node (ref "R27") (pin "1") (pinfunction "1_1") (pintype "passive"))
      (node (ref "U$15") (pin "U_HN") (pinfunction "U_HN_U_HN") (pintype "bidirectional"))
      (node (ref "U$15") (pin "V_HN") (pinfunction "V_HN_V_HN") (pintype "bidirectional"))
      (node (ref "U$15") (pin "W_HN") (pinfunction "W_HN_W_HN") (pintype "bidirectional"))
    )
    (net (code "66") (name "Net-(R31-Pad2)") (class "Default")
      (node (ref "R31") (pin "2") (pinfunction "2_2") (pintype "passive"))
      (node (ref "U$15") (pin "CS") (pinfunction "CS_CS") (pintype "bidirectional"))
    )
    (net (code "67") (name "Net-(U$3-PadSBWTCK)") (class "Default")
      (node (ref "U$3") (pin "SBWTCK") (pinfunction "SBWTCK_SBWTCK") (pintype "bidirectional"))
      (node (ref "U$4") (pin "SBWTCK") (pinfunction "SBWTCK_SBWTCK") (pintype "bidirectional"))
    )
    (net (code "68") (name "Net-(U$4-P2.0_TXD)") (class "Default")
      (node (ref "U$3") (pin "P2.0_TXD") (pinfunction "P2.0_TXD_P2.0_TXD") (pintype "bidirectional"))
      (node (ref "U$4") (pin "3") (pinfunction "P2.0_TXD_3") (pintype "bidirectional"))
    )
    (net (code "69") (name "Net-(U$4-P2.1_RXD)") (class "Default")
      (node (ref "U$3") (pin "P2.1_RXD") (pinfunction "P2.1_RXD_P2.1_RXD") (pintype "bidirectional"))
      (node (ref "U$4") (pin "4") (pinfunction "P2.1_RXD_4") (pintype "bidirectional"))
    )
    (net (code "70") (name "Net-(U$4-P3.4_GPIO_DEBUG)") (class "Default")
      (node (ref "U$3") (pin "P3.4_GPIO_DEBUG") (pinfunction "P3.4_GPIO_DEBUG_P3.4_GPIO_DEBUG") (pintype "bidirectional"))
      (node (ref "U$4") (pin "7") (pinfunction "P3.4_GPIO_DEBUG_7") (pintype "bidirectional"))
    )
    (net (code "71") (name "Net-(U$4-P3.5_GPIO_DEBUG)") (class "Default")
      (node (ref "U$3") (pin "P3.5_GPIO_DEBUG") (pinfunction "P3.5_GPIO_DEBUG_P3.5_GPIO_DEBUG") (pintype "bidirectional"))
      (node (ref "U$4") (pin "8") (pinfunction "P3.5_GPIO_DEBUG_8") (pintype "bidirectional"))
    )
    (net (code "72") (name "Net-(U$4-SBWTDIO)") (class "Default")
      (node (ref "U$3") (pin "SBWTDIO") (pinfunction "SBWTDIO_SBWTDIO") (pintype "bidirectional"))
      (node (ref "U$4") (pin "2") (pinfunction "SBWTDIO_2") (pintype "bidirectional"))
    )
    (net (code "73") (name "Net-(U$5-EN{slash}UVLO)") (class "Default")
      (node (ref "R12") (pin "2") (pinfunction "2_2") (pintype "passive"))
      (node (ref "U$5") (pin "P$8") (pinfunction "EN/UVLO_P$8") (pintype "bidirectional"))
    )
    (net (code "74") (name "Net-(U$5-FBX)") (class "Default")
      (node (ref "C27") (pin "2") (pinfunction "2_2") (pintype "passive"))
      (node (ref "R13") (pin "1") (pinfunction "1_1") (pintype "passive"))
      (node (ref "R14") (pin "2") (pinfunction "2_2") (pintype "passive"))
      (node (ref "U$5") (pin "P$1") (pinfunction "FBX_P$1") (pintype "bidirectional"))
    )
    (net (code "75") (name "Net-(U$5-INT_VCC)") (class "Default")
      (node (ref "C24") (pin "1") (pinfunction "1_1") (pintype "passive"))
      (node (ref "U$5") (pin "P$7") (pinfunction "INT_VCC_P$7") (pintype "bidirectional"))
    )
    (net (code "76") (name "Net-(U$10-PadSBWTCK)") (class "Default")
      (node (ref "U$10") (pin "SBWTCK") (pinfunction "SBWTCK_SBWTCK") (pintype "bidirectional"))
      (node (ref "U$11") (pin "SBWTCK") (pinfunction "SBWTCK_SBWTCK") (pintype "bidirectional"))
    )
    (net (code "77") (name "Net-(U$11-P2.0_TXD)") (class "Default")
      (node (ref "U$10") (pin "P2.0_TXD") (pinfunction "P2.0_TXD_P2.0_TXD") (pintype "bidirectional"))
      (node (ref "U$11") (pin "3") (pinfunction "P2.0_TXD_3") (pintype "bidirectional"))
    )
    (net (code "78") (name "Net-(U$11-P2.1_RXD)") (class "Default")
      (node (ref "U$10") (pin "P2.1_RXD") (pinfunction "P2.1_RXD_P2.1_RXD") (pintype "bidirectional"))
      (node (ref "U$11") (pin "4") (pinfunction "P2.1_RXD_4") (pintype "bidirectional"))
    )
    (net (code "79") (name "Net-(U$11-P3.4_GPIO_DEBUG)") (class "Default")
      (node (ref "U$10") (pin "P3.4_GPIO_DEBUG") (pinfunction "P3.4_GPIO_DEBUG_P3.4_GPIO_DEBUG") (pintype "bidirectional"))
      (node (ref "U$11") (pin "7") (pinfunction "P3.4_GPIO_DEBUG_7") (pintype "bidirectional"))
    )
    (net (code "80") (name "Net-(U$11-P3.5_GPIO_DEBUG)") (class "Default")
      (node (ref "U$10") (pin "P3.5_GPIO_DEBUG") (pinfunction "P3.5_GPIO_DEBUG_P3.5_GPIO_DEBUG") (pintype "bidirectional"))
      (node (ref "U$11") (pin "8") (pinfunction "P3.5_GPIO_DEBUG_8") (pintype "bidirectional"))
    )
    (net (code "81") (name "Net-(U$11-SBWTDIO)") (class "Default")
      (node (ref "U$10") (pin "SBWTDIO") (pinfunction "SBWTDIO_SBWTDIO") (pintype "bidirectional"))
      (node (ref "U$11") (pin "2") (pinfunction "SBWTDIO_2") (pintype "bidirectional"))
    )
    (net (code "82") (name "Net-(U$13-PadSBWTCK)") (class "Default")
      (node (ref "U$13") (pin "SBWTCK") (pinfunction "SBWTCK_SBWTCK") (pintype "bidirectional"))
      (node (ref "U$14") (pin "SBWTCK") (pinfunction "SBWTCK_SBWTCK") (pintype "bidirectional"))
    )
    (net (code "83") (name "Net-(U$14-P2.0_TXD)") (class "Default")
      (node (ref "U$13") (pin "P2.0_TXD") (pinfunction "P2.0_TXD_P2.0_TXD") (pintype "bidirectional"))
      (node (ref "U$14") (pin "3") (pinfunction "P2.0_TXD_3") (pintype "bidirectional"))
    )
    (net (code "84") (name "Net-(U$14-P2.1_RXD)") (class "Default")
      (node (ref "U$13") (pin "P2.1_RXD") (pinfunction "P2.1_RXD_P2.1_RXD") (pintype "bidirectional"))
      (node (ref "U$14") (pin "4") (pinfunction "P2.1_RXD_4") (pintype "bidirectional"))
    )
    (net (code "85") (name "Net-(U$14-P3.4_GPIO_DEBUG)") (class "Default")
      (node (ref "U$13") (pin "P3.4_GPIO_DEBUG") (pinfunction "P3.4_GPIO_DEBUG_P3.4_GPIO_DEBUG") (pintype "bidirectional"))
      (node (ref "U$14") (pin "7") (pinfunction "P3.4_GPIO_DEBUG_7") (pintype "bidirectional"))
    )
    (net (code "86") (name "Net-(U$14-P3.5_GPIO_DEBUG)") (class "Default")
      (node (ref "U$13") (pin "P3.5_GPIO_DEBUG") (pinfunction "P3.5_GPIO_DEBUG_P3.5_GPIO_DEBUG") (pintype "bidirectional"))
      (node (ref "U$14") (pin "8") (pinfunction "P3.5_GPIO_DEBUG_8") (pintype "bidirectional"))
    )
    (net (code "87") (name "Net-(U$14-SBWTDIO)") (class "Default")
      (node (ref "U$13") (pin "SBWTDIO") (pinfunction "SBWTDIO_SBWTDIO") (pintype "bidirectional"))
      (node (ref "U$14") (pin "2") (pinfunction "SBWTDIO_2") (pintype "bidirectional"))
    )
    (net (code "88") (name "PWM_X") (class "Default")
      (node (ref "U$3") (pin "P1.7_GPIO/PWM") (pinfunction "P1.7_GPIO/PWM_P1.7_GPIO/PWM") (pintype "bidirectional"))
      (node (ref "U$7") (pin "PWM") (pinfunction "PWM_PWM") (pintype "bidirectional"))
    )
    (net (code "89") (name "PWM_Y") (class "Default")
      (node (ref "U$10") (pin "P1.7_GPIO/PWM") (pinfunction "P1.7_GPIO/PWM_P1.7_GPIO/PWM") (pintype "bidirectional"))
      (node (ref "U$12") (pin "PWM") (pinfunction "PWM_PWM") (pintype "bidirectional"))
    )
    (net (code "90") (name "PWM_Z") (class "Default")
      (node (ref "U$13") (pin "P1.7_GPIO/PWM") (pinfunction "P1.7_GPIO/PWM_P1.7_GPIO/PWM") (pintype "bidirectional"))
      (node (ref "U$15") (pin "PWM") (pinfunction "PWM_PWM") (pintype "bidirectional"))
    )
    (net (code "91") (name "RD_X") (class "Default")
      (node (ref "R1") (pin "1") (pinfunction "1_1") (pintype "passive"))
      (node (ref "U$3") (pin "P4.0_GPIO") (pinfunction "P4.0_GPIO_P4.0_GPIO") (pintype "bidirectional"))
      (node (ref "U$7") (pin "RD") (pinfunction "RD_RD") (pintype "bidirectional"))
    )
    (net (code "92") (name "RD_Y") (class "Default")
      (node (ref "R17") (pin "1") (pinfunction "1_1") (pintype "passive"))
      (node (ref "U$10") (pin "P4.0_GPIO") (pinfunction "P4.0_GPIO_P4.0_GPIO") (pintype "bidirectional"))
      (node (ref "U$12") (pin "RD") (pinfunction "RD_RD") (pintype "bidirectional"))
    )
    (net (code "93") (name "RD_Z") (class "Default")
      (node (ref "R25") (pin "1") (pinfunction "1_1") (pintype "passive"))
      (node (ref "U$13") (pin "P4.0_GPIO") (pinfunction "P4.0_GPIO_P4.0_GPIO") (pintype "bidirectional"))
      (node (ref "U$15") (pin "RD") (pinfunction "RD_RD") (pintype "bidirectional"))
    )
    (net (code "94") (name "SYNC1") (class "Default")
      (node (ref "U$10") (pin "P7.2_SYNC1") (pinfunction "P7.2_SYNC1_P7.2_SYNC1") (pintype "bidirectional"))
      (node (ref "U$13") (pin "P7.2_SYNC1") (pinfunction "P7.2_SYNC1_P7.2_SYNC1") (pintype "bidirectional"))
      (node (ref "U$2") (pin "P$45") (pinfunction "SYNC1_P$45") (pintype "bidirectional"))
      (node (ref "U$3") (pin "P7.2_SYNC1") (pinfunction "P7.2_SYNC1_P7.2_SYNC1") (pintype "bidirectional"))
    )
    (net (code "95") (name "SYNC2") (class "Default")
      (node (ref "U$10") (pin "PJ.3_SYNC2") (pinfunction "PJ.3_SYNC2_PJ.3_SYNC2") (pintype "bidirectional"))
      (node (ref "U$13") (pin "PJ.3_SYNC2") (pinfunction "PJ.3_SYNC2_PJ.3_SYNC2") (pintype "bidirectional"))
      (node (ref "U$2") (pin "P$49") (pinfunction "SYNC2_P$49") (pintype "bidirectional"))
      (node (ref "U$3") (pin "PJ.3_SYNC2") (pinfunction "PJ.3_SYNC2_PJ.3_SYNC2") (pintype "bidirectional"))
    )
    (net (code "96") (name "VBAT") (class "Default")
      (node (ref "C23") (pin "1") (pinfunction "1_1") (pintype "passive"))
      (node (ref "L2") (pin "P$4") (pinfunction "2B_P$4") (pintype "bidirectional"))
      (node (ref "LDO_3V3") (pin "P$1") (pinfunction "IN_P$1") (pintype "bidirectional"))
      (node (ref "LDO_5V") (pin "P$1") (pinfunction "IN_P$1") (pintype "bidirectional"))
      (node (ref "R12") (pin "1") (pinfunction "1_1") (pintype "passive"))
      (node (ref "U$2") (pin "P$81") (pinfunction "BDOT_5V_P$81") (pintype "bidirectional"))
      (node (ref "U$2") (pin "P$83") (pinfunction "BDOT_3.3V_P$83") (pintype "bidirectional"))
      (node (ref "U$5") (pin "P$6") (pinfunction "V_IN_P$6") (pintype "bidirectional"))
    )
    (net (code "97") (name "VINT_X") (class "Default")
      (node (ref "C4") (pin "2") (pinfunction "2_2") (pintype "passive"))
      (node (ref "CMTMOD_X") (pin "P$3") (pinfunction "VCC_P$3") (pintype "bidirectional"))
      (node (ref "DAA_X") (pin "P$3") (pinfunction "VCC_P$3") (pintype "bidirectional"))
      (node (ref "MOTOR_X") (pin "P$5") (pinfunction "P$5_P$5") (pintype "bidirectional"))
      (node (ref "R1") (pin "2") (pinfunction "2_2") (pintype "passive"))
      (node (ref "R3") (pin "2") (pinfunction "2_2") (pintype "passive"))
      (node (ref "R4") (pin "1") (pinfunction "1_1") (pintype "passive"))
      (node (ref "R5") (pin "1") (pinfunction "1_1") (pintype "passive"))
      (node (ref "R6") (pin "1") (pinfunction "1_1") (pintype "passive"))
      (node (ref "R8") (pin "1") (pinfunction "1_1") (pintype "passive"))
      (node (ref "U$7") (pin "VINT") (pinfunction "VINT_VINT") (pintype "bidirectional"))
    )
    (net (code "98") (name "VINT_Y") (class "Default")
      (node (ref "C14") (pin "2") (pinfunction "2_2") (pintype "passive"))
      (node (ref "CMTMOD_Y") (pin "P$3") (pinfunction "VCC_P$3") (pintype "bidirectional"))
      (node (ref "DAA_Y") (pin "P$3") (pinfunction "VCC_P$3") (pintype "bidirectional"))
      (node (ref "MOTOR_Y") (pin "P$5") (pinfunction "P$5_P$5") (pintype "bidirectional"))
      (node (ref "R17") (pin "2") (pinfunction "2_2") (pintype "passive"))
      (node (ref "R19") (pin "2") (pinfunction "2_2") (pintype "passive"))
      (node (ref "R20") (pin "1") (pinfunction "1_1") (pintype "passive"))
      (node (ref "R21") (pin "1") (pinfunction "1_1") (pintype "passive"))
      (node (ref "R22") (pin "1") (pinfunction "1_1") (pintype "passive"))
      (node (ref "R24") (pin "1") (pinfunction "1_1") (pintype "passive"))
      (node (ref "U$12") (pin "VINT") (pinfunction "VINT_VINT") (pintype "bidirectional"))
    )
    (net (code "99") (name "VINT_Z") (class "Default")
      (node (ref "C21") (pin "2") (pinfunction "2_2") (pintype "passive"))
      (node (ref "CMTMOD_Z") (pin "P$3") (pinfunction "VCC_P$3") (pintype "bidirectional"))
      (node (ref "DAA_Z") (pin "P$3") (pinfunction "VCC_P$3") (pintype "bidirectional"))
      (node (ref "MOTOR_Z") (pin "P$5") (pinfunction "P$5_P$5") (pintype "bidirectional"))
      (node (ref "R25") (pin "2") (pinfunction "2_2") (pintype "passive"))
      (node (ref "R27") (pin "2") (pinfunction "2_2") (pintype "passive"))
      (node (ref "R28") (pin "1") (pinfunction "1_1") (pintype "passive"))
      (node (ref "R29") (pin "1") (pinfunction "1_1") (pintype "passive"))
      (node (ref "R30") (pin "1") (pinfunction "1_1") (pintype "passive"))
      (node (ref "R32") (pin "1") (pinfunction "1_1") (pintype "passive"))
      (node (ref "U$15") (pin "VINT") (pinfunction "VINT_VINT") (pintype "bidirectional"))
    )
    (net (code "100") (name "VM") (class "Default")
      (node (ref "C15") (pin "2") (pinfunction "2_2") (pintype "passive"))
      (node (ref "C22") (pin "2") (pinfunction "2_2") (pintype "passive"))
      (node (ref "C26") (pin "1") (pinfunction "1_1") (pintype "passive"))
      (node (ref "C27") (pin "1") (pinfunction "1_1") (pintype "passive"))
      (node (ref "C5") (pin "2") (pinfunction "2_2") (pintype "passive"))
      (node (ref "D2") (pin "P$2") (pinfunction "-_P$2") (pintype "bidirectional"))
      (node (ref "R13") (pin "2") (pinfunction "2_2") (pintype "passive"))
      (node (ref "U$12") (pin "VM") (pinfunction "VM_VM") (pintype "bidirectional"))
      (node (ref "U$15") (pin "VM") (pinfunction "VM_VM") (pintype "bidirectional"))
      (node (ref "U$7") (pin "VM") (pinfunction "VM_VM") (pintype "bidirectional"))
    )
    (net (code "101") (name "unconnected-(LDO_3V3-EN-PadP$3)") (class "Default")
      (node (ref "LDO_3V3") (pin "P$3") (pinfunction "EN_P$3") (pintype "bidirectional"))
    )
    (net (code "102") (name "unconnected-(LDO_5V-EN-PadP$3)") (class "Default")
      (node (ref "LDO_5V") (pin "P$3") (pinfunction "EN_P$3") (pintype "bidirectional"))
    )
    (net (code "103") (name "unconnected-(U$2-3.3V-PadP$54)") (class "Default")
      (node (ref "U$2") (pin "P$54") (pinfunction "3.3V_P$54") (pintype "bidirectional"))
    )
    (net (code "104") (name "unconnected-(U$2-3.3V-PadP$55)") (class "Default")
      (node (ref "U$2") (pin "P$55") (pinfunction "3.3V_P$55") (pintype "bidirectional"))
    )
    (net (code "105") (name "unconnected-(U$2-5V-PadP$50)") (class "Default")
      (node (ref "U$2") (pin "P$50") (pinfunction "5V_P$50") (pintype "bidirectional"))
    )
    (net (code "106") (name "unconnected-(U$2-5V-PadP$51)") (class "Default")
      (node (ref "U$2") (pin "P$51") (pinfunction "5V_P$51") (pintype "bidirectional"))
    )
    (net (code "107") (name "unconnected-(U$2-BDOT_GND-PadP$87)") (class "Default")
      (node (ref "U$2") (pin "P$87") (pinfunction "BDOT_GND_P$87") (pintype "bidirectional"))
    )
    (net (code "108") (name "unconnected-(U$2-BDOT_GND-PadP$88)") (class "Default")
      (node (ref "U$2") (pin "P$88") (pinfunction "BDOT_GND_P$88") (pintype "bidirectional"))
    )
    (net (code "109") (name "unconnected-(U$2-BDOT_VBAT-PadP$85)") (class "Default")
      (node (ref "U$2") (pin "P$85") (pinfunction "BDOT_VBAT_P$85") (pintype "bidirectional"))
    )
    (net (code "110") (name "unconnected-(U$2-BDOT_VBAT-PadP$86)") (class "Default")
      (node (ref "U$2") (pin "P$86") (pinfunction "BDOT_VBAT_P$86") (pintype "bidirectional"))
    )
    (net (code "111") (name "unconnected-(U$2-COM1_GND-PadP$102)") (class "Default")
      (node (ref "U$2") (pin "P$102") (pinfunction "COM1_GND_P$102") (pintype "bidirectional"))
    )
    (net (code "112") (name "unconnected-(U$2-COM1_GND-PadP$104)") (class "Default")
      (node (ref "U$2") (pin "P$104") (pinfunction "COM1_GND_P$104") (pintype "bidirectional"))
    )
    (net (code "113") (name "unconnected-(U$2-COM1_VBAT-PadP$101)") (class "Default")
      (node (ref "U$2") (pin "P$101") (pinfunction "COM1_VBAT_P$101") (pintype "bidirectional"))
    )
    (net (code "114") (name "unconnected-(U$2-COM1_VBAT-PadP$103)") (class "Default")
      (node (ref "U$2") (pin "P$103") (pinfunction "COM1_VBAT_P$103") (pintype "bidirectional"))
    )
    (net (code "115") (name "unconnected-(U$2-COM2_GND-PadP$98)") (class "Default")
      (node (ref "U$2") (pin "P$98") (pinfunction "COM2_GND_P$98") (pintype "bidirectional"))
    )
    (net (code "116") (name "unconnected-(U$2-COM2_GND-PadP$100)") (class "Default")
      (node (ref "U$2") (pin "P$100") (pinfunction "COM2_GND_P$100") (pintype "bidirectional"))
    )
    (net (code "117") (name "unconnected-(U$2-COM2_VBAT-PadP$97)") (class "Default")
      (node (ref "U$2") (pin "P$97") (pinfunction "COM2_VBAT_P$97") (pintype "bidirectional"))
    )
    (net (code "118") (name "unconnected-(U$2-COM2_VBAT-PadP$99)") (class "Default")
      (node (ref "U$2") (pin "P$99") (pinfunction "COM2_VBAT_P$99") (pintype "bidirectional"))
    )
    (net (code "119") (name "unconnected-(U$2-DISTRI_GND-PadP$17)") (class "Default")
      (node (ref "U$2") (pin "P$17") (pinfunction "DISTRI_GND_P$17") (pintype "bidirectional"))
    )
    (net (code "120") (name "unconnected-(U$2-DISTRI_GND-PadP$19)") (class "Default")
      (node (ref "U$2") (pin "P$19") (pinfunction "DISTRI_GND_P$19") (pintype "bidirectional"))
    )
    (net (code "121") (name "unconnected-(U$2-DISTRI_GND-PadP$22)") (class "Default")
      (node (ref "U$2") (pin "P$22") (pinfunction "DISTRI_GND_P$22") (pintype "bidirectional"))
    )
    (net (code "122") (name "unconnected-(U$2-DISTRI_GND-PadP$24)") (class "Default")
      (node (ref "U$2") (pin "P$24") (pinfunction "DISTRI_GND_P$24") (pintype "bidirectional"))
    )
    (net (code "123") (name "unconnected-(U$2-DISTRI_GND-PadP$25)") (class "Default")
      (node (ref "U$2") (pin "P$25") (pinfunction "DISTRI_GND_P$25") (pintype "bidirectional"))
    )
    (net (code "124") (name "unconnected-(U$2-DISTRI_GND-PadP$27)") (class "Default")
      (node (ref "U$2") (pin "P$27") (pinfunction "DISTRI_GND_P$27") (pintype "bidirectional"))
    )
    (net (code "125") (name "unconnected-(U$2-DISTRI_GND-PadP$30)") (class "Default")
      (node (ref "U$2") (pin "P$30") (pinfunction "DISTRI_GND_P$30") (pintype "bidirectional"))
    )
    (net (code "126") (name "unconnected-(U$2-DISTRI_GND-PadP$32)") (class "Default")
      (node (ref "U$2") (pin "P$32") (pinfunction "DISTRI_GND_P$32") (pintype "bidirectional"))
    )
    (net (code "127") (name "unconnected-(U$2-DISTRI_VBAT-PadP$18)") (class "Default")
      (node (ref "U$2") (pin "P$18") (pinfunction "DISTRI_VBAT_P$18") (pintype "bidirectional"))
    )
    (net (code "128") (name "unconnected-(U$2-DISTRI_VBAT-PadP$20)") (class "Default")
      (node (ref "U$2") (pin "P$20") (pinfunction "DISTRI_VBAT_P$20") (pintype "bidirectional"))
    )
    (net (code "129") (name "unconnected-(U$2-DISTRI_VBAT-PadP$21)") (class "Default")
      (node (ref "U$2") (pin "P$21") (pinfunction "DISTRI_VBAT_P$21") (pintype "bidirectional"))
    )
    (net (code "130") (name "unconnected-(U$2-DISTRI_VBAT-PadP$23)") (class "Default")
      (node (ref "U$2") (pin "P$23") (pinfunction "DISTRI_VBAT_P$23") (pintype "bidirectional"))
    )
    (net (code "131") (name "unconnected-(U$2-DISTRI_VBAT-PadP$26)") (class "Default")
      (node (ref "U$2") (pin "P$26") (pinfunction "DISTRI_VBAT_P$26") (pintype "bidirectional"))
    )
    (net (code "132") (name "unconnected-(U$2-DISTRI_VBAT-PadP$28)") (class "Default")
      (node (ref "U$2") (pin "P$28") (pinfunction "DISTRI_VBAT_P$28") (pintype "bidirectional"))
    )
    (net (code "133") (name "unconnected-(U$2-DISTRI_VBAT-PadP$29)") (class "Default")
      (node (ref "U$2") (pin "P$29") (pinfunction "DISTRI_VBAT_P$29") (pintype "bidirectional"))
    )
    (net (code "134") (name "unconnected-(U$2-DISTRI_VBAT-PadP$31)") (class "Default")
      (node (ref "U$2") (pin "P$31") (pinfunction "DISTRI_VBAT_P$31") (pintype "bidirectional"))
    )
    (net (code "135") (name "unconnected-(U$2-ESTIMAT_3.3V-PadP$75)") (class "Default")
      (node (ref "U$2") (pin "P$75") (pinfunction "ESTIMAT_3.3V_P$75") (pintype "bidirectional"))
    )
    (net (code "136") (name "unconnected-(U$2-ESTIMAT_3.3V-PadP$76)") (class "Default")
      (node (ref "U$2") (pin "P$76") (pinfunction "ESTIMAT_3.3V_P$76") (pintype "bidirectional"))
    )
    (net (code "137") (name "unconnected-(U$2-ESTIMAT_5V-PadP$73)") (class "Default")
      (node (ref "U$2") (pin "P$73") (pinfunction "ESTIMAT_5V_P$73") (pintype "bidirectional"))
    )
    (net (code "138") (name "unconnected-(U$2-ESTIMAT_5V-PadP$74)") (class "Default")
      (node (ref "U$2") (pin "P$74") (pinfunction "ESTIMAT_5V_P$74") (pintype "bidirectional"))
    )
    (net (code "139") (name "unconnected-(U$2-ESTIMAT_GND-PadP$79)") (class "Default")
      (node (ref "U$2") (pin "P$79") (pinfunction "ESTIMAT_GND_P$79") (pintype "bidirectional"))
    )
    (net (code "140") (name "unconnected-(U$2-ESTIMAT_GND-PadP$80)") (class "Default")
      (node (ref "U$2") (pin "P$80") (pinfunction "ESTIMAT_GND_P$80") (pintype "bidirectional"))
    )
    (net (code "141") (name "unconnected-(U$2-ESTIMAT_VBAT-PadP$77)") (class "Default")
      (node (ref "U$2") (pin "P$77") (pinfunction "ESTIMAT_VBAT_P$77") (pintype "bidirectional"))
    )
    (net (code "142") (name "unconnected-(U$2-ESTIMAT_VBAT-PadP$78)") (class "Default")
      (node (ref "U$2") (pin "P$78") (pinfunction "ESTIMAT_VBAT_P$78") (pintype "bidirectional"))
    )
    (net (code "143") (name "unconnected-(U$2-MCU_GND-PadP$46)") (class "Default")
      (node (ref "U$2") (pin "P$46") (pinfunction "MCU_GND_P$46") (pintype "bidirectional"))
    )
    (net (code "144") (name "unconnected-(U$2-MCU_GND-PadP$47)") (class "Default")
      (node (ref "U$2") (pin "P$47") (pinfunction "MCU_GND_P$47") (pintype "bidirectional"))
    )
    (net (code "145") (name "unconnected-(U$2-MCU_GND-PadP$58)") (class "Default")
      (node (ref "U$2") (pin "P$58") (pinfunction "MCU_GND_P$58") (pintype "bidirectional"))
    )
    (net (code "146") (name "unconnected-(U$2-MCU_GND-PadP$59)") (class "Default")
      (node (ref "U$2") (pin "P$59") (pinfunction "MCU_GND_P$59") (pintype "bidirectional"))
    )
    (net (code "147") (name "unconnected-(U$2-PPT_GND-PadP$1)") (class "Default")
      (node (ref "U$2") (pin "P$1") (pinfunction "PPT_GND_P$1") (pintype "bidirectional"))
    )
    (net (code "148") (name "unconnected-(U$2-PPT_GND-PadP$3)") (class "Default")
      (node (ref "U$2") (pin "P$3") (pinfunction "PPT_GND_P$3") (pintype "bidirectional"))
    )
    (net (code "149") (name "unconnected-(U$2-PPT_GND-PadP$6)") (class "Default")
      (node (ref "U$2") (pin "P$6") (pinfunction "PPT_GND_P$6") (pintype "bidirectional"))
    )
    (net (code "150") (name "unconnected-(U$2-PPT_GND-PadP$8)") (class "Default")
      (node (ref "U$2") (pin "P$8") (pinfunction "PPT_GND_P$8") (pintype "bidirectional"))
    )
    (net (code "151") (name "unconnected-(U$2-PPT_GND-PadP$9)") (class "Default")
      (node (ref "U$2") (pin "P$9") (pinfunction "PPT_GND_P$9") (pintype "bidirectional"))
    )
    (net (code "152") (name "unconnected-(U$2-PPT_GND-PadP$11)") (class "Default")
      (node (ref "U$2") (pin "P$11") (pinfunction "PPT_GND_P$11") (pintype "bidirectional"))
    )
    (net (code "153") (name "unconnected-(U$2-PPT_GND-PadP$14)") (class "Default")
      (node (ref "U$2") (pin "P$14") (pinfunction "PPT_GND_P$14") (pintype "bidirectional"))
    )
    (net (code "154") (name "unconnected-(U$2-PPT_GND-PadP$16)") (class "Default")
      (node (ref "U$2") (pin "P$16") (pinfunction "PPT_GND_P$16") (pintype "bidirectional"))
    )
    (net (code "155") (name "unconnected-(U$2-PPT_VBAT-PadP$2)") (class "Default")
      (node (ref "U$2") (pin "P$2") (pinfunction "PPT_VBAT_P$2") (pintype "bidirectional"))
    )
    (net (code "156") (name "unconnected-(U$2-PPT_VBAT-PadP$4)") (class "Default")
      (node (ref "U$2") (pin "P$4") (pinfunction "PPT_VBAT_P$4") (pintype "bidirectional"))
    )
    (net (code "157") (name "unconnected-(U$2-PPT_VBAT-PadP$5)") (class "Default")
      (node (ref "U$2") (pin "P$5") (pinfunction "PPT_VBAT_P$5") (pintype "bidirectional"))
    )
    (net (code "158") (name "unconnected-(U$2-PPT_VBAT-PadP$7)") (class "Default")
      (node (ref "U$2") (pin "P$7") (pinfunction "PPT_VBAT_P$7") (pintype "bidirectional"))
    )
    (net (code "159") (name "unconnected-(U$2-PPT_VBAT-PadP$10)") (class "Default")
      (node (ref "U$2") (pin "P$10") (pinfunction "PPT_VBAT_P$10") (pintype "bidirectional"))
    )
    (net (code "160") (name "unconnected-(U$2-PPT_VBAT-PadP$12)") (class "Default")
      (node (ref "U$2") (pin "P$12") (pinfunction "PPT_VBAT_P$12") (pintype "bidirectional"))
    )
    (net (code "161") (name "unconnected-(U$2-PPT_VBAT-PadP$13)") (class "Default")
      (node (ref "U$2") (pin "P$13") (pinfunction "PPT_VBAT_P$13") (pintype "bidirectional"))
    )
    (net (code "162") (name "unconnected-(U$2-PPT_VBAT-PadP$15)") (class "Default")
      (node (ref "U$2") (pin "P$15") (pinfunction "PPT_VBAT_P$15") (pintype "bidirectional"))
    )
    (net (code "163") (name "unconnected-(U$2-PadP$33)") (class "Default")
      (node (ref "U$2") (pin "P$33") (pinfunction "P$33_P$33") (pintype "bidirectional"))
    )
    (net (code "164") (name "unconnected-(U$2-PadP$34)") (class "Default")
      (node (ref "U$2") (pin "P$34") (pinfunction "P$34_P$34") (pintype "bidirectional"))
    )
    (net (code "165") (name "unconnected-(U$2-PadP$35)") (class "Default")
      (node (ref "U$2") (pin "P$35") (pinfunction "P$35_P$35") (pintype "bidirectional"))
    )
    (net (code "166") (name "unconnected-(U$2-PadP$36)") (class "Default")
      (node (ref "U$2") (pin "P$36") (pinfunction "P$36_P$36") (pintype "bidirectional"))
    )
    (net (code "167") (name "unconnected-(U$2-PadP$37)") (class "Default")
      (node (ref "U$2") (pin "P$37") (pinfunction "P$37_P$37") (pintype "bidirectional"))
    )
    (net (code "168") (name "unconnected-(U$2-PadP$38)") (class "Default")
      (node (ref "U$2") (pin "P$38") (pinfunction "P$38_P$38") (pintype "bidirectional"))
    )
    (net (code "169") (name "unconnected-(U$2-PadP$39)") (class "Default")
      (node (ref "U$2") (pin "P$39") (pinfunction "P$39_P$39") (pintype "bidirectional"))
    )
    (net (code "170") (name "unconnected-(U$2-PadP$40)") (class "Default")
      (node (ref "U$2") (pin "P$40") (pinfunction "P$40_P$40") (pintype "bidirectional"))
    )
    (net (code "171") (name "unconnected-(U$2-PadP$41)") (class "Default")
      (node (ref "U$2") (pin "P$41") (pinfunction "P$41_P$41") (pintype "bidirectional"))
    )
    (net (code "172") (name "unconnected-(U$2-PadP$42)") (class "Default")
      (node (ref "U$2") (pin "P$42") (pinfunction "P$42_P$42") (pintype "bidirectional"))
    )
    (net (code "173") (name "unconnected-(U$2-PadP$43)") (class "Default")
      (node (ref "U$2") (pin "P$43") (pinfunction "P$43_P$43") (pintype "bidirectional"))
    )
    (net (code "174") (name "unconnected-(U$2-PadP$44)") (class "Default")
      (node (ref "U$2") (pin "P$44") (pinfunction "P$44_P$44") (pintype "bidirectional"))
    )
    (net (code "175") (name "unconnected-(U$2-PadP$48)") (class "Default")
      (node (ref "U$2") (pin "P$48") (pinfunction "P$48_P$48") (pintype "bidirectional"))
    )
    (net (code "176") (name "unconnected-(U$2-PadP$52)") (class "Default")
      (node (ref "U$2") (pin "P$52") (pinfunction "P$52_P$52") (pintype "bidirectional"))
    )
    (net (code "177") (name "unconnected-(U$2-PadP$56)") (class "Default")
      (node (ref "U$2") (pin "P$56") (pinfunction "P$56_P$56") (pintype "bidirectional"))
    )
    (net (code "178") (name "unconnected-(U$2-PadP$60)") (class "Default")
      (node (ref "U$2") (pin "P$60") (pinfunction "P$60_P$60") (pintype "bidirectional"))
    )
    (net (code "179") (name "unconnected-(U$2-PadP$61)") (class "Default")
      (node (ref "U$2") (pin "P$61") (pinfunction "P$61_P$61") (pintype "bidirectional"))
    )
    (net (code "180") (name "unconnected-(U$2-PadP$62)") (class "Default")
      (node (ref "U$2") (pin "P$62") (pinfunction "P$62_P$62") (pintype "bidirectional"))
    )
    (net (code "181") (name "unconnected-(U$2-PadP$63)") (class "Default")
      (node (ref "U$2") (pin "P$63") (pinfunction "P$63_P$63") (pintype "bidirectional"))
    )
    (net (code "182") (name "unconnected-(U$2-PadP$64)") (class "Default")
      (node (ref "U$2") (pin "P$64") (pinfunction "P$64_P$64") (pintype "bidirectional"))
    )
    (net (code "183") (name "unconnected-(U$2-PadP$65)") (class "Default")
      (node (ref "U$2") (pin "P$65") (pinfunction "P$65_P$65") (pintype "bidirectional"))
    )
    (net (code "184") (name "unconnected-(U$2-PadP$66)") (class "Default")
      (node (ref "U$2") (pin "P$66") (pinfunction "P$66_P$66") (pintype "bidirectional"))
    )
    (net (code "185") (name "unconnected-(U$2-PadP$67)") (class "Default")
      (node (ref "U$2") (pin "P$67") (pinfunction "P$67_P$67") (pintype "bidirectional"))
    )
    (net (code "186") (name "unconnected-(U$2-PadP$68)") (class "Default")
      (node (ref "U$2") (pin "P$68") (pinfunction "P$68_P$68") (pintype "bidirectional"))
    )
    (net (code "187") (name "unconnected-(U$2-PadP$89)") (class "Default")
      (node (ref "U$2") (pin "P$89") (pinfunction "P$89_P$89") (pintype "bidirectional"))
    )
    (net (code "188") (name "unconnected-(U$2-PadP$90)") (class "Default")
      (node (ref "U$2") (pin "P$90") (pinfunction "P$90_P$90") (pintype "bidirectional"))
    )
    (net (code "189") (name "unconnected-(U$2-PadP$91)") (class "Default")
      (node (ref "U$2") (pin "P$91") (pinfunction "P$91_P$91") (pintype "bidirectional"))
    )
    (net (code "190") (name "unconnected-(U$2-PadP$92)") (class "Default")
      (node (ref "U$2") (pin "P$92") (pinfunction "P$92_P$92") (pintype "bidirectional"))
    )
    (net (code "191") (name "unconnected-(U$2-PadP$95)") (class "Default")
      (node (ref "U$2") (pin "P$95") (pinfunction "P$95_P$95") (pintype "bidirectional"))
    )
    (net (code "192") (name "unconnected-(U$2-PadP$96)") (class "Default")
      (node (ref "U$2") (pin "P$96") (pinfunction "P$96_P$96") (pintype "bidirectional"))
    )
    (net (code "193") (name "unconnected-(U$2-RAHS_GND-PadP$94)") (class "Default")
      (node (ref "U$2") (pin "P$94") (pinfunction "RAHS_GND_P$94") (pintype "bidirectional"))
    )
    (net (code "194") (name "unconnected-(U$2-RAHS_VBAT-PadP$93)") (class "Default")
      (node (ref "U$2") (pin "P$93") (pinfunction "RAHS_VBAT_P$93") (pintype "bidirectional"))
    )
    (net (code "195") (name "unconnected-(U$2-WHEEL_GND-PadP$71)") (class "Default")
      (node (ref "U$2") (pin "P$71") (pinfunction "WHEEL_GND_P$71") (pintype "bidirectional"))
    )
    (net (code "196") (name "unconnected-(U$2-WHEEL_GND-PadP$72)") (class "Default")
      (node (ref "U$2") (pin "P$72") (pinfunction "WHEEL_GND_P$72") (pintype "bidirectional"))
    )
    (net (code "197") (name "unconnected-(U$2-WHEEL_VBATT-PadP$69)") (class "Default")
      (node (ref "U$2") (pin "P$69") (pinfunction "WHEEL_VBATT_P$69") (pintype "bidirectional"))
    )
    (net (code "198") (name "unconnected-(U$2-WHEEL_VBATT-PadP$70)") (class "Default")
      (node (ref "U$2") (pin "P$70") (pinfunction "WHEEL_VBATT_P$70") (pintype "bidirectional"))
    )
    (net (code "199") (name "unconnected-(U$3-P2.3_SPI-CS2-PadP2.4_SPI-CS2)") (class "Default")
      (node (ref "U$3") (pin "P2.4_SPI-CS2") (pinfunction "P2.3_SPI-CS2_P2.4_SPI-CS2") (pintype "bidirectional"))
    )
    (net (code "200") (name "unconnected-(U$3-PadP1.0_A0)") (class "Default")
      (node (ref "U$3") (pin "P1.0_A0") (pinfunction "P1.0_A0_P1.0_A0") (pintype "bidirectional"))
    )
    (net (code "201") (name "unconnected-(U$3-PadP1.1_A1)") (class "Default")
      (node (ref "U$3") (pin "P1.1_A1") (pinfunction "P1.1_A1_P1.1_A1") (pintype "bidirectional"))
    )
    (net (code "202") (name "unconnected-(U$3-PadP1.2_A2)") (class "Default")
      (node (ref "U$3") (pin "P1.2_A2") (pinfunction "P1.2_A2_P1.2_A2") (pintype "bidirectional"))
    )
    (net (code "203") (name "unconnected-(U$3-PadP1.3_A3)") (class "Default")
      (node (ref "U$3") (pin "P1.3_A3") (pinfunction "P1.3_A3_P1.3_A3") (pintype "bidirectional"))
    )
    (net (code "204") (name "unconnected-(U$3-PadP1.4_A4)") (class "Default")
      (node (ref "U$3") (pin "P1.4_A4") (pinfunction "P1.4_A4_P1.4_A4") (pintype "bidirectional"))
    )
    (net (code "205") (name "unconnected-(U$3-PadP1.5_A5)") (class "Default")
      (node (ref "U$3") (pin "P1.5_A5") (pinfunction "P1.5_A5_P1.5_A5") (pintype "bidirectional"))
    )
    (net (code "206") (name "unconnected-(U$3-PadP1.6_GPIO{slash}PWM)") (class "Default")
      (node (ref "U$3") (pin "P1.6_GPIO/PWM") (pinfunction "P1.6_GPIO/PWM_P1.6_GPIO/PWM") (pintype "bidirectional"))
    )
    (net (code "207") (name "unconnected-(U$3-PadP2.2_GPIO{slash}PWM)") (class "Default")
      (node (ref "U$3") (pin "P2.2_GPIO/PWM") (pinfunction "P2.2_GPIO/PWM_P2.2_GPIO/PWM") (pintype "bidirectional"))
    )
    (net (code "208") (name "unconnected-(U$3-PadP2.7_SPI-CS3)") (class "Default")
      (node (ref "U$3") (pin "P2.7_SPI-CS3") (pinfunction "P2.7_SPI-CS3_P2.7_SPI-CS3") (pintype "bidirectional"))
    )
    (net (code "209") (name "unconnected-(U$3-PadP3.0_A12)") (class "Default")
      (node (ref "U$3") (pin "P3.0_A12") (pinfunction "P3.0_A12_P3.0_A12") (pintype "bidirectional"))
    )
    (net (code "210") (name "unconnected-(U$3-PadP3.1_A13)") (class "Default")
      (node (ref "U$3") (pin "P3.1_A13") (pinfunction "P3.1_A13_P3.1_A13") (pintype "bidirectional"))
    )
    (net (code "211") (name "unconnected-(U$3-PadP3.2_A14)") (class "Default")
      (node (ref "U$3") (pin "P3.2_A14") (pinfunction "P3.2_A14_P3.2_A14") (pintype "bidirectional"))
    )
    (net (code "212") (name "unconnected-(U$3-PadP3.3_A15)") (class "Default")
      (node (ref "U$3") (pin "P3.3_A15") (pinfunction "P3.3_A15_P3.3_A15") (pintype "bidirectional"))
    )
    (net (code "213") (name "unconnected-(U$3-PadP3.6_GPIO{slash}PWM)") (class "Default")
      (node (ref "U$3") (pin "P3.6_GPIO/PWM") (pinfunction "P3.6_GPIO/PWM_P3.6_GPIO/PWM") (pintype "bidirectional"))
    )
    (net (code "214") (name "unconnected-(U$3-PadP3.7_GPIO{slash}PWM)") (class "Default")
      (node (ref "U$3") (pin "P3.7_GPIO/PWM") (pinfunction "P3.7_GPIO/PWM_P3.7_GPIO/PWM") (pintype "bidirectional"))
    )
    (net (code "215") (name "unconnected-(U$3-PadP4.1_GPIO)") (class "Default")
      (node (ref "U$3") (pin "P4.1_GPIO") (pinfunction "P4.1_GPIO_P4.1_GPIO") (pintype "bidirectional"))
    )
    (net (code "216") (name "unconnected-(U$3-PadP4.2_GPIO)") (class "Default")
      (node (ref "U$3") (pin "P4.2_GPIO") (pinfunction "P4.2_GPIO_P4.2_GPIO") (pintype "bidirectional"))
    )
    (net (code "217") (name "unconnected-(U$3-PadP5.0_I2C-SDA-1)") (class "Default")
      (node (ref "U$3") (pin "P5.0_I2C-SDA-1") (pinfunction "P5.0_I2C-SDA-1_P5.0_I2C-SDA-1") (pintype "bidirectional"))
    )
    (net (code "218") (name "unconnected-(U$3-PadP5.1_I2C-SCL-1)") (class "Default")
      (node (ref "U$3") (pin "P5.1_I2C-SCL-1") (pinfunction "P5.1_I2C-SCL-1_P5.1_I2C-SCL-1") (pintype "bidirectional"))
    )
    (net (code "219") (name "unconnected-(U$3-PadP5.4_SPI-MOSI)") (class "Default")
      (node (ref "U$3") (pin "P5.4_SPI-MOSI") (pinfunction "P5.4_SPI-MOSI_P5.4_SPI-MOSI") (pintype "bidirectional"))
    )
    (net (code "220") (name "unconnected-(U$3-PadP5.5_SPI-MISO)") (class "Default")
      (node (ref "U$3") (pin "P5.5_SPI-MISO") (pinfunction "P5.5_SPI-MISO_P5.5_SPI-MISO") (pintype "bidirectional"))
    )
    (net (code "221") (name "unconnected-(U$3-PadP5.6_SPI-CLK)") (class "Default")
      (node (ref "U$3") (pin "P5.6_SPI-CLK") (pinfunction "P5.6_SPI-CLK_P5.6_SPI-CLK") (pintype "bidirectional"))
    )
    (net (code "222") (name "unconnected-(U$3-PadP7.0_I2C-SDA-2)") (class "Default")
      (node (ref "U$3") (pin "P7.0_I2C-SDA-2") (pinfunction "P7.0_I2C-SDA-2_P7.0_I2C-SDA-2") (pintype "bidirectional"))
    )
    (net (code "223") (name "unconnected-(U$3-PadP7.1_I2C-SCL-2)") (class "Default")
      (node (ref "U$3") (pin "P7.1_I2C-SCL-2") (pinfunction "P7.1_I2C-SCL-2_P7.1_I2C-SCL-2") (pintype "bidirectional"))
    )
    (net (code "224") (name "unconnected-(U$5-NC-PadP$2)") (class "Default")
      (node (ref "U$5") (pin "P$2") (pinfunction "NC_P$2") (pintype "bidirectional"))
    )
    (net (code "225") (name "unconnected-(U$10-P2.3_SPI-CS2-PadP2.4_SPI-CS2)") (class "Default")
      (node (ref "U$10") (pin "P2.4_SPI-CS2") (pinfunction "P2.3_SPI-CS2_P2.4_SPI-CS2") (pintype "bidirectional"))
    )
    (net (code "226") (name "unconnected-(U$10-PadP1.0_A0)") (class "Default")
      (node (ref "U$10") (pin "P1.0_A0") (pinfunction "P1.0_A0_P1.0_A0") (pintype "bidirectional"))
    )
    (net (code "227") (name "unconnected-(U$10-PadP1.1_A1)") (class "Default")
      (node (ref "U$10") (pin "P1.1_A1") (pinfunction "P1.1_A1_P1.1_A1") (pintype "bidirectional"))
    )
    (net (code "228") (name "unconnected-(U$10-PadP1.2_A2)") (class "Default")
      (node (ref "U$10") (pin "P1.2_A2") (pinfunction "P1.2_A2_P1.2_A2") (pintype "bidirectional"))
    )
    (net (code "229") (name "unconnected-(U$10-PadP1.3_A3)") (class "Default")
      (node (ref "U$10") (pin "P1.3_A3") (pinfunction "P1.3_A3_P1.3_A3") (pintype "bidirectional"))
    )
    (net (code "230") (name "unconnected-(U$10-PadP1.4_A4)") (class "Default")
      (node (ref "U$10") (pin "P1.4_A4") (pinfunction "P1.4_A4_P1.4_A4") (pintype "bidirectional"))
    )
    (net (code "231") (name "unconnected-(U$10-PadP1.5_A5)") (class "Default")
      (node (ref "U$10") (pin "P1.5_A5") (pinfunction "P1.5_A5_P1.5_A5") (pintype "bidirectional"))
    )
    (net (code "232") (name "unconnected-(U$10-PadP1.6_GPIO{slash}PWM)") (class "Default")
      (node (ref "U$10") (pin "P1.6_GPIO/PWM") (pinfunction "P1.6_GPIO/PWM_P1.6_GPIO/PWM") (pintype "bidirectional"))
    )
    (net (code "233") (name "unconnected-(U$10-PadP2.2_GPIO{slash}PWM)") (class "Default")
      (node (ref "U$10") (pin "P2.2_GPIO/PWM") (pinfunction "P2.2_GPIO/PWM_P2.2_GPIO/PWM") (pintype "bidirectional"))
    )
    (net (code "234") (name "unconnected-(U$10-PadP2.7_SPI-CS3)") (class "Default")
      (node (ref "U$10") (pin "P2.7_SPI-CS3") (pinfunction "P2.7_SPI-CS3_P2.7_SPI-CS3") (pintype "bidirectional"))
    )
    (net (code "235") (name "unconnected-(U$10-PadP3.0_A12)") (class "Default")
      (node (ref "U$10") (pin "P3.0_A12") (pinfunction "P3.0_A12_P3.0_A12") (pintype "bidirectional"))
    )
    (net (code "236") (name "unconnected-(U$10-PadP3.1_A13)") (class "Default")
      (node (ref "U$10") (pin "P3.1_A13") (pinfunction "P3.1_A13_P3.1_A13") (pintype "bidirectional"))
    )
    (net (code "237") (name "unconnected-(U$10-PadP3.2_A14)") (class "Default")
      (node (ref "U$10") (pin "P3.2_A14") (pinfunction "P3.2_A14_P3.2_A14") (pintype "bidirectional"))
    )
    (net (code "238") (name "unconnected-(U$10-PadP3.3_A15)") (class "Default")
      (node (ref "U$10") (pin "P3.3_A15") (pinfunction "P3.3_A15_P3.3_A15") (pintype "bidirectional"))
    )
    (net (code "239") (name "unconnected-(U$10-PadP3.6_GPIO{slash}PWM)") (class "Default")
      (node (ref "U$10") (pin "P3.6_GPIO/PWM") (pinfunction "P3.6_GPIO/PWM_P3.6_GPIO/PWM") (pintype "bidirectional"))
    )
    (net (code "240") (name "unconnected-(U$10-PadP3.7_GPIO{slash}PWM)") (class "Default")
      (node (ref "U$10") (pin "P3.7_GPIO/PWM") (pinfunction "P3.7_GPIO/PWM_P3.7_GPIO/PWM") (pintype "bidirectional"))
    )
    (net (code "241") (name "unconnected-(U$10-PadP4.1_GPIO)") (class "Default")
      (node (ref "U$10") (pin "P4.1_GPIO") (pinfunction "P4.1_GPIO_P4.1_GPIO") (pintype "bidirectional"))
    )
    (net (code "242") (name "unconnected-(U$10-PadP4.2_GPIO)") (class "Default")
      (node (ref "U$10") (pin "P4.2_GPIO") (pinfunction "P4.2_GPIO_P4.2_GPIO") (pintype "bidirectional"))
    )
    (net (code "243") (name "unconnected-(U$10-PadP5.0_I2C-SDA-1)") (class "Default")
      (node (ref "U$10") (pin "P5.0_I2C-SDA-1") (pinfunction "P5.0_I2C-SDA-1_P5.0_I2C-SDA-1") (pintype "bidirectional"))
    )
    (net (code "244") (name "unconnected-(U$10-PadP5.1_I2C-SCL-1)") (class "Default")
      (node (ref "U$10") (pin "P5.1_I2C-SCL-1") (pinfunction "P5.1_I2C-SCL-1_P5.1_I2C-SCL-1") (pintype "bidirectional"))
    )
    (net (code "245") (name "unconnected-(U$10-PadP5.4_SPI-MOSI)") (class "Default")
      (node (ref "U$10") (pin "P5.4_SPI-MOSI") (pinfunction "P5.4_SPI-MOSI_P5.4_SPI-MOSI") (pintype "bidirectional"))
    )
    (net (code "246") (name "unconnected-(U$10-PadP5.5_SPI-MISO)") (class "Default")
      (node (ref "U$10") (pin "P5.5_SPI-MISO") (pinfunction "P5.5_SPI-MISO_P5.5_SPI-MISO") (pintype "bidirectional"))
    )
    (net (code "247") (name "unconnected-(U$10-PadP5.6_SPI-CLK)") (class "Default")
      (node (ref "U$10") (pin "P5.6_SPI-CLK") (pinfunction "P5.6_SPI-CLK_P5.6_SPI-CLK") (pintype "bidirectional"))
    )
    (net (code "248") (name "unconnected-(U$10-PadP7.0_I2C-SDA-2)") (class "Default")
      (node (ref "U$10") (pin "P7.0_I2C-SDA-2") (pinfunction "P7.0_I2C-SDA-2_P7.0_I2C-SDA-2") (pintype "bidirectional"))
    )
    (net (code "249") (name "unconnected-(U$10-PadP7.1_I2C-SCL-2)") (class "Default")
      (node (ref "U$10") (pin "P7.1_I2C-SCL-2") (pinfunction "P7.1_I2C-SCL-2_P7.1_I2C-SCL-2") (pintype "bidirectional"))
    )
    (net (code "250") (name "unconnected-(U$13-P2.3_SPI-CS2-PadP2.4_SPI-CS2)") (class "Default")
      (node (ref "U$13") (pin "P2.4_SPI-CS2") (pinfunction "P2.3_SPI-CS2_P2.4_SPI-CS2") (pintype "bidirectional"))
    )
    (net (code "251") (name "unconnected-(U$13-PadP1.0_A0)") (class "Default")
      (node (ref "U$13") (pin "P1.0_A0") (pinfunction "P1.0_A0_P1.0_A0") (pintype "bidirectional"))
    )
    (net (code "252") (name "unconnected-(U$13-PadP1.1_A1)") (class "Default")
      (node (ref "U$13") (pin "P1.1_A1") (pinfunction "P1.1_A1_P1.1_A1") (pintype "bidirectional"))
    )
    (net (code "253") (name "unconnected-(U$13-PadP1.2_A2)") (class "Default")
      (node (ref "U$13") (pin "P1.2_A2") (pinfunction "P1.2_A2_P1.2_A2") (pintype "bidirectional"))
    )
    (net (code "254") (name "unconnected-(U$13-PadP1.3_A3)") (class "Default")
      (node (ref "U$13") (pin "P1.3_A3") (pinfunction "P1.3_A3_P1.3_A3") (pintype "bidirectional"))
    )
    (net (code "255") (name "unconnected-(U$13-PadP1.4_A4)") (class "Default")
      (node (ref "U$13") (pin "P1.4_A4") (pinfunction "P1.4_A4_P1.4_A4") (pintype "bidirectional"))
    )
    (net (code "256") (name "unconnected-(U$13-PadP1.5_A5)") (class "Default")
      (node (ref "U$13") (pin "P1.5_A5") (pinfunction "P1.5_A5_P1.5_A5") (pintype "bidirectional"))
    )
    (net (code "257") (name "unconnected-(U$13-PadP1.6_GPIO{slash}PWM)") (class "Default")
      (node (ref "U$13") (pin "P1.6_GPIO/PWM") (pinfunction "P1.6_GPIO/PWM_P1.6_GPIO/PWM") (pintype "bidirectional"))
    )
    (net (code "258") (name "unconnected-(U$13-PadP2.2_GPIO{slash}PWM)") (class "Default")
      (node (ref "U$13") (pin "P2.2_GPIO/PWM") (pinfunction "P2.2_GPIO/PWM_P2.2_GPIO/PWM") (pintype "bidirectional"))
    )
    (net (code "259") (name "unconnected-(U$13-PadP2.7_SPI-CS3)") (class "Default")
      (node (ref "U$13") (pin "P2.7_SPI-CS3") (pinfunction "P2.7_SPI-CS3_P2.7_SPI-CS3") (pintype "bidirectional"))
    )
    (net (code "260") (name "unconnected-(U$13-PadP3.0_A12)") (class "Default")
      (node (ref "U$13") (pin "P3.0_A12") (pinfunction "P3.0_A12_P3.0_A12") (pintype "bidirectional"))
    )
    (net (code "261") (name "unconnected-(U$13-PadP3.1_A13)") (class "Default")
      (node (ref "U$13") (pin "P3.1_A13") (pinfunction "P3.1_A13_P3.1_A13") (pintype "bidirectional"))
    )
    (net (code "262") (name "unconnected-(U$13-PadP3.2_A14)") (class "Default")
      (node (ref "U$13") (pin "P3.2_A14") (pinfunction "P3.2_A14_P3.2_A14") (pintype "bidirectional"))
    )
    (net (code "263") (name "unconnected-(U$13-PadP3.3_A15)") (class "Default")
      (node (ref "U$13") (pin "P3.3_A15") (pinfunction "P3.3_A15_P3.3_A15") (pintype "bidirectional"))
    )
    (net (code "264") (name "unconnected-(U$13-PadP3.6_GPIO{slash}PWM)") (class "Default")
      (node (ref "U$13") (pin "P3.6_GPIO/PWM") (pinfunction "P3.6_GPIO/PWM_P3.6_GPIO/PWM") (pintype "bidirectional"))
    )
    (net (code "265") (name "unconnected-(U$13-PadP3.7_GPIO{slash}PWM)") (class "Default")
      (node (ref "U$13") (pin "P3.7_GPIO/PWM") (pinfunction "P3.7_GPIO/PWM_P3.7_GPIO/PWM") (pintype "bidirectional"))
    )
    (net (code "266") (name "unconnected-(U$13-PadP4.1_GPIO)") (class "Default")
      (node (ref "U$13") (pin "P4.1_GPIO") (pinfunction "P4.1_GPIO_P4.1_GPIO") (pintype "bidirectional"))
    )
    (net (code "267") (name "unconnected-(U$13-PadP4.2_GPIO)") (class "Default")
      (node (ref "U$13") (pin "P4.2_GPIO") (pinfunction "P4.2_GPIO_P4.2_GPIO") (pintype "bidirectional"))
    )
    (net (code "268") (name "unconnected-(U$13-PadP5.0_I2C-SDA-1)") (class "Default")
      (node (ref "U$13") (pin "P5.0_I2C-SDA-1") (pinfunction "P5.0_I2C-SDA-1_P5.0_I2C-SDA-1") (pintype "bidirectional"))
    )
    (net (code "269") (name "unconnected-(U$13-PadP5.1_I2C-SCL-1)") (class "Default")
      (node (ref "U$13") (pin "P5.1_I2C-SCL-1") (pinfunction "P5.1_I2C-SCL-1_P5.1_I2C-SCL-1") (pintype "bidirectional"))
    )
    (net (code "270") (name "unconnected-(U$13-PadP5.4_SPI-MOSI)") (class "Default")
      (node (ref "U$13") (pin "P5.4_SPI-MOSI") (pinfunction "P5.4_SPI-MOSI_P5.4_SPI-MOSI") (pintype "bidirectional"))
    )
    (net (code "271") (name "unconnected-(U$13-PadP5.5_SPI-MISO)") (class "Default")
      (node (ref "U$13") (pin "P5.5_SPI-MISO") (pinfunction "P5.5_SPI-MISO_P5.5_SPI-MISO") (pintype "bidirectional"))
    )
    (net (code "272") (name "unconnected-(U$13-PadP5.6_SPI-CLK)") (class "Default")
      (node (ref "U$13") (pin "P5.6_SPI-CLK") (pinfunction "P5.6_SPI-CLK_P5.6_SPI-CLK") (pintype "bidirectional"))
    )
    (net (code "273") (name "unconnected-(U$13-PadP7.0_I2C-SDA-2)") (class "Default")
      (node (ref "U$13") (pin "P7.0_I2C-SDA-2") (pinfunction "P7.0_I2C-SDA-2_P7.0_I2C-SDA-2") (pintype "bidirectional"))
    )
    (net (code "274") (name "unconnected-(U$13-PadP7.1_I2C-SCL-2)") (class "Default")
      (node (ref "U$13") (pin "P7.1_I2C-SCL-2") (pinfunction "P7.1_I2C-SCL-2_P7.1_I2C-SCL-2") (pintype "bidirectional"))
    )
  )
)
